# PWR_DC_DC_EXAR.net
KiCad netlist of a schematic drawn in Altium Designer
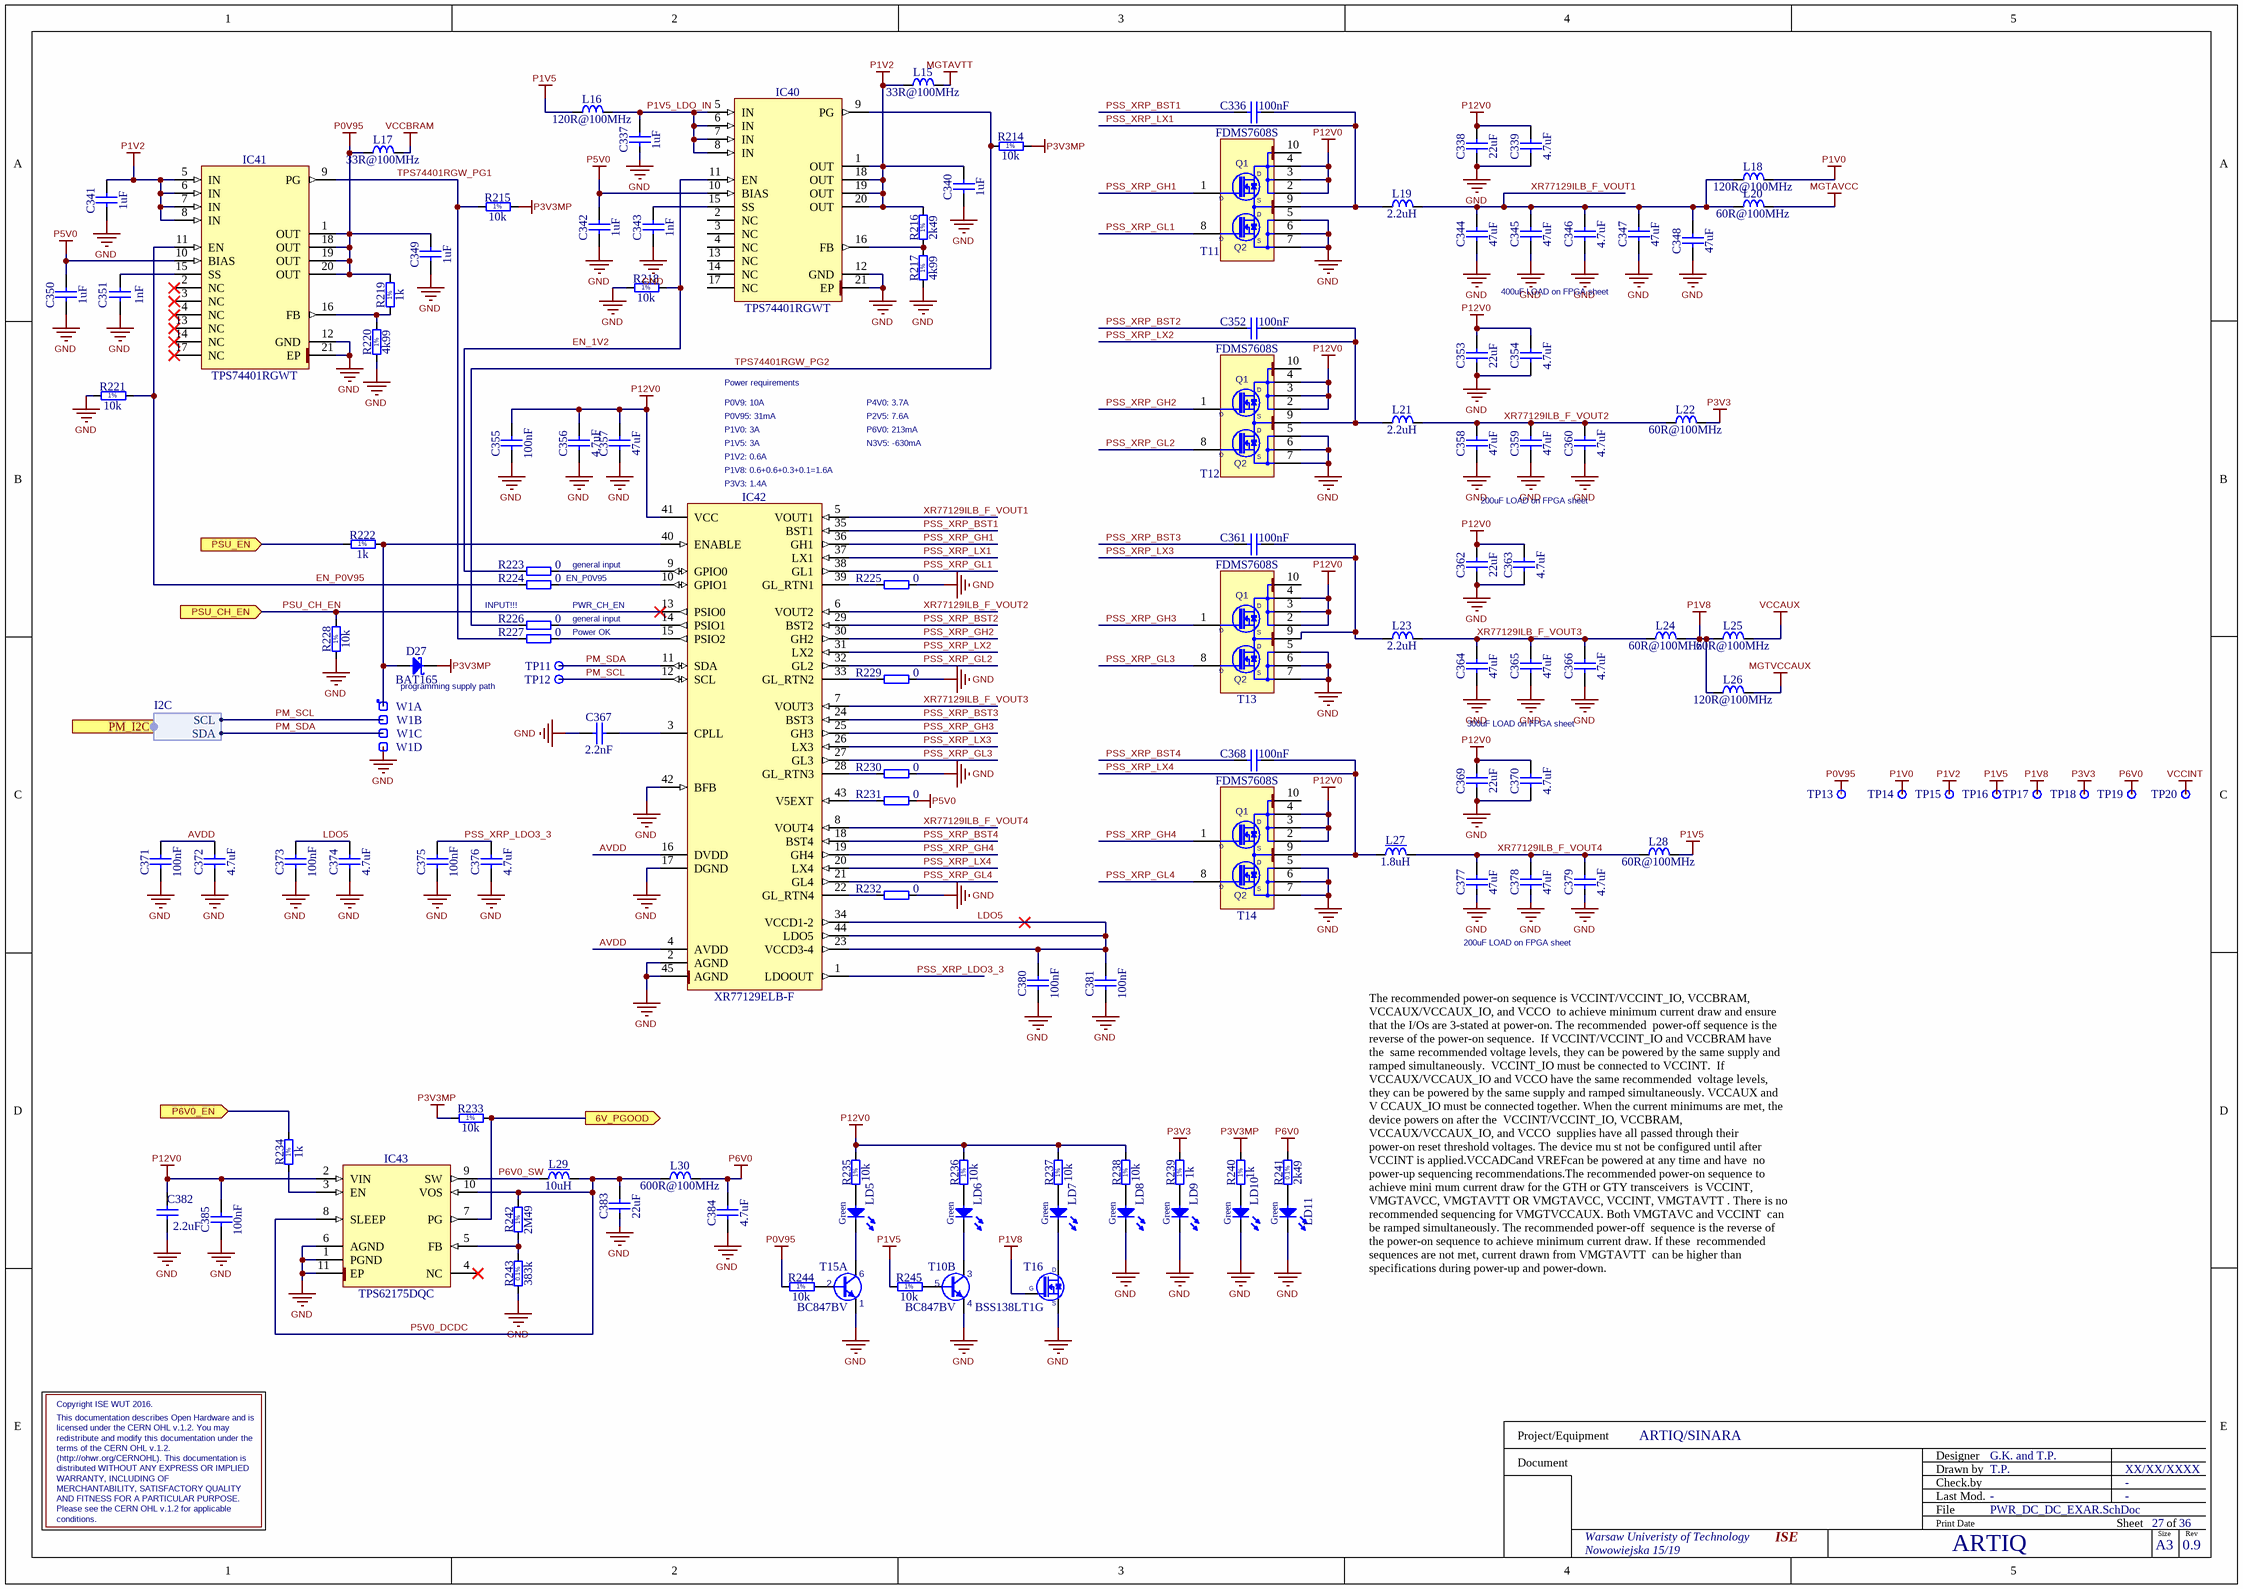
[diagram p0: PWR_DC_DC_EXAR.SchDoc]

(export (version "E")
  (design (tool "Eeschema 10.0.6"))
  (components
    (comp (ref "C336")
      (value "100nF")
      (footprint "CAPC1005X55N")
      (description "Non-polarised capacitor")
      (fields
        (field (name "MANUFACTURER PART NUMBER") "CC0402_100NF_16V_10%_X5R")
        (field (name "MANUFACTURER") "GENERIC")
        (field (name "AUTHOR") "CERN DEM JLC")
      )
      (libsource (lib "Capacitors") (part "Capacitor - non polarized"))
    )
    (comp (ref "C337")
      (value "1uF")
      (footprint "CAPC1005X55N")
      (description "Non-polarised capacitor")
      (fields
        (field (name "MANUFACTURER PART NUMBER") "CC0402_1UF_16V_10%_X5R")
        (field (name "MANUFACTURER") "GENERIC")
        (field (name "AUTHOR") "CERN DEM JLC")
      )
      (libsource (lib "Capacitors") (part "Capacitor - non polarized"))
    )
    (comp (ref "C338")
      (value "22uF")
      (footprint "CAPC2012X135N")
      (description "Non-polarised capacitor")
      (fields
        (field (name "MANUFACTURER PART NUMBER") "CC0805_22UF_16V_10%_X5R")
        (field (name "MANUFACTURER") "GENERIC")
        (field (name "AUTHOR") "CERN DEM JLC")
      )
      (libsource (lib "Capacitors") (part "Capacitor - non polarized"))
    )
    (comp (ref "C339")
      (value "4.7uF")
      (footprint "CAPC1709X95N")
      (description "Non-polarised capacitor")
      (fields
        (field (name "MANUFACTURER PART NUMBER") "CC0603_4.7UF_16V_10%_X5R")
        (field (name "MANUFACTURER") "GENERIC")
        (field (name "AUTHOR") "CERN DEM JLC")
      )
      (libsource (lib "Capacitors") (part "Capacitor - non polarized"))
    )
    (comp (ref "C340")
      (value "1uF")
      (footprint "CAPC1005X55N")
      (description "Non-polarised capacitor")
      (fields
        (field (name "MANUFACTURER PART NUMBER") "CC0402_1UF_16V_10%_X5R")
        (field (name "MANUFACTURER") "GENERIC")
        (field (name "AUTHOR") "CERN DEM JLC")
      )
      (libsource (lib "Capacitors") (part "Capacitor - non polarized"))
    )
    (comp (ref "C341")
      (value "1uF")
      (footprint "CAPC1005X55N")
      (description "Non-polarised capacitor")
      (fields
        (field (name "MANUFACTURER PART NUMBER") "CC0402_1UF_16V_10%_X5R")
        (field (name "MANUFACTURER") "GENERIC")
        (field (name "AUTHOR") "CERN DEM JLC")
      )
      (libsource (lib "Capacitors") (part "Capacitor - non polarized"))
    )
    (comp (ref "C342")
      (value "1uF")
      (footprint "CAPC1005X55N")
      (description "Non-polarised capacitor")
      (fields
        (field (name "MANUFACTURER PART NUMBER") "CC0402_1UF_16V_10%_X5R")
        (field (name "MANUFACTURER") "GENERIC")
        (field (name "AUTHOR") "CERN DEM JLC")
      )
      (libsource (lib "Capacitors") (part "Capacitor - non polarized"))
    )
    (comp (ref "C343")
      (value "1nF")
      (footprint "CAPC1005X55N")
      (description "Non-polarised capacitor")
      (fields
        (field (name "MANUFACTURER PART NUMBER") "CC0402_1NF_50V_10%_X7R")
        (field (name "MANUFACTURER") "GENERIC")
        (field (name "AUTHOR") "CERN DEM JLC")
      )
      (libsource (lib "Capacitors") (part "Capacitor - non polarized"))
    )
    (comp (ref "C344")
      (value "47uF")
      (footprint "CAPC2012X140N")
      (description "Non-polarised capacitor")
      (fields
        (field (name "MANUFACTURER PART NUMBER") "CC0805_47UF_6.3V_20%_X5R")
        (field (name "MANUFACTURER") "GENERIC")
        (field (name "AUTHOR") "CERN DEM JLC")
      )
      (libsource (lib "Capacitors") (part "Capacitor - non polarized"))
    )
    (comp (ref "C345")
      (value "47uF")
      (footprint "CAPC2012X140N")
      (description "Non-polarised capacitor")
      (fields
        (field (name "MANUFACTURER PART NUMBER") "CC0805_47UF_6.3V_20%_X5R")
        (field (name "MANUFACTURER") "GENERIC")
        (field (name "AUTHOR") "CERN DEM JLC")
      )
      (libsource (lib "Capacitors") (part "Capacitor - non polarized"))
    )
    (comp (ref "C346")
      (value "4.7uF")
      (footprint "CAPC1709X95N")
      (description "Non-polarised capacitor")
      (fields
        (field (name "MANUFACTURER PART NUMBER") "CC0603_4.7UF_16V_10%_X5R")
        (field (name "MANUFACTURER") "GENERIC")
        (field (name "AUTHOR") "CERN DEM JLC")
      )
      (libsource (lib "Capacitors") (part "Capacitor - non polarized"))
    )
    (comp (ref "C347")
      (value "47uF")
      (footprint "CAPC2012X140N")
      (description "Non-polarised capacitor")
      (fields
        (field (name "MANUFACTURER PART NUMBER") "CC0805_47UF_6.3V_20%_X5R")
        (field (name "MANUFACTURER") "GENERIC")
        (field (name "AUTHOR") "CERN DEM JLC")
      )
      (libsource (lib "Capacitors") (part "Capacitor - non polarized"))
    )
    (comp (ref "C348")
      (value "47uF")
      (footprint "CAPC2012X140N")
      (description "Non-polarised capacitor")
      (fields
        (field (name "MANUFACTURER PART NUMBER") "CC0805_47UF_6.3V_20%_X5R")
        (field (name "MANUFACTURER") "GENERIC")
        (field (name "AUTHOR") "CERN DEM JLC")
      )
      (libsource (lib "Capacitors") (part "Capacitor - non polarized"))
    )
    (comp (ref "C349")
      (value "1uF")
      (footprint "CAPC1005X55N")
      (description "Non-polarised capacitor")
      (fields
        (field (name "MANUFACTURER PART NUMBER") "CC0402_1UF_16V_10%_X5R")
        (field (name "MANUFACTURER") "GENERIC")
        (field (name "AUTHOR") "CERN DEM JLC")
      )
      (libsource (lib "Capacitors") (part "Capacitor - non polarized"))
    )
    (comp (ref "C350")
      (value "1uF")
      (footprint "CAPC1005X55N")
      (description "Non-polarised capacitor")
      (fields
        (field (name "MANUFACTURER PART NUMBER") "CC0402_1UF_16V_10%_X5R")
        (field (name "MANUFACTURER") "GENERIC")
        (field (name "AUTHOR") "CERN DEM JLC")
      )
      (libsource (lib "Capacitors") (part "Capacitor - non polarized"))
    )
    (comp (ref "C351")
      (value "1nF")
      (footprint "CAPC1005X55N")
      (description "Non-polarised capacitor")
      (fields
        (field (name "MANUFACTURER PART NUMBER") "CC0402_1NF_50V_10%_X7R")
        (field (name "MANUFACTURER") "GENERIC")
        (field (name "AUTHOR") "CERN DEM JLC")
      )
      (libsource (lib "Capacitors") (part "Capacitor - non polarized"))
    )
    (comp (ref "C352")
      (value "100nF")
      (footprint "CAPC1005X55N")
      (description "Non-polarised capacitor")
      (fields
        (field (name "MANUFACTURER PART NUMBER") "CC0402_100NF_16V_10%_X5R")
        (field (name "MANUFACTURER") "GENERIC")
        (field (name "AUTHOR") "CERN DEM JLC")
      )
      (libsource (lib "Capacitors") (part "Capacitor - non polarized"))
    )
    (comp (ref "C353")
      (value "22uF")
      (footprint "CAPC2012X135N")
      (description "Non-polarised capacitor")
      (fields
        (field (name "MANUFACTURER PART NUMBER") "CC0805_22UF_16V_10%_X5R")
        (field (name "MANUFACTURER") "GENERIC")
        (field (name "AUTHOR") "CERN DEM JLC")
      )
      (libsource (lib "Capacitors") (part "Capacitor - non polarized"))
    )
    (comp (ref "C354")
      (value "4.7uF")
      (footprint "CAPC1709X95N")
      (description "Non-polarised capacitor")
      (fields
        (field (name "MANUFACTURER PART NUMBER") "CC0603_4.7UF_16V_10%_X5R")
        (field (name "MANUFACTURER") "GENERIC")
        (field (name "AUTHOR") "CERN DEM JLC")
      )
      (libsource (lib "Capacitors") (part "Capacitor - non polarized"))
    )
    (comp (ref "C355")
      (value "100nF")
      (footprint "CAPC1005X55N")
      (description "Non-polarised capacitor")
      (fields
        (field (name "MANUFACTURER PART NUMBER") "CC0402_100NF_16V_10%_X5R")
        (field (name "MANUFACTURER") "GENERIC")
        (field (name "AUTHOR") "CERN DEM JLC")
      )
      (libsource (lib "Capacitors") (part "Capacitor - non polarized"))
    )
    (comp (ref "C356")
      (value "4.7uF")
      (footprint "CAPC1709X95N")
      (description "Non-polarised capacitor")
      (fields
        (field (name "MANUFACTURER PART NUMBER") "CC0603_4.7UF_16V_10%_X5R")
        (field (name "MANUFACTURER") "GENERIC")
        (field (name "AUTHOR") "CERN DEM JLC")
      )
      (libsource (lib "Capacitors") (part "Capacitor - non polarized"))
    )
    (comp (ref "C357")
      (value "47uF")
      (footprint "CAPC3216X180N")
      (description "Non-polarised capacitor")
      (fields
        (field (name "MANUFACTURER PART NUMBER") "CC1206_47UF_25V_20%_X5R")
        (field (name "MANUFACTURER") "GENERIC")
        (field (name "AUTHOR") "CERN DEM JLC")
      )
      (libsource (lib "Capacitors") (part "Capacitor - non polarized"))
    )
    (comp (ref "C358")
      (value "47uF")
      (footprint "CAPC2012X140N")
      (description "Non-polarised capacitor")
      (fields
        (field (name "MANUFACTURER PART NUMBER") "CC0805_47UF_6.3V_20%_X5R")
        (field (name "MANUFACTURER") "GENERIC")
        (field (name "AUTHOR") "CERN DEM JLC")
      )
      (libsource (lib "Capacitors") (part "Capacitor - non polarized"))
    )
    (comp (ref "C359")
      (value "47uF")
      (footprint "CAPC2012X140N")
      (description "Non-polarised capacitor")
      (fields
        (field (name "MANUFACTURER PART NUMBER") "CC0805_47UF_6.3V_20%_X5R")
        (field (name "MANUFACTURER") "GENERIC")
        (field (name "AUTHOR") "CERN DEM JLC")
      )
      (libsource (lib "Capacitors") (part "Capacitor - non polarized"))
    )
    (comp (ref "C360")
      (value "4.7uF")
      (footprint "CAPC1709X95N")
      (description "Non-polarised capacitor")
      (fields
        (field (name "MANUFACTURER PART NUMBER") "CC0603_4.7UF_16V_10%_X5R")
        (field (name "MANUFACTURER") "GENERIC")
        (field (name "AUTHOR") "CERN DEM JLC")
      )
      (libsource (lib "Capacitors") (part "Capacitor - non polarized"))
    )
    (comp (ref "C361")
      (value "100nF")
      (footprint "CAPC1005X55N")
      (description "Non-polarised capacitor")
      (fields
        (field (name "MANUFACTURER PART NUMBER") "CC0402_100NF_16V_10%_X5R")
        (field (name "MANUFACTURER") "GENERIC")
        (field (name "AUTHOR") "CERN DEM JLC")
      )
      (libsource (lib "Capacitors") (part "Capacitor - non polarized"))
    )
    (comp (ref "C362")
      (value "22uF")
      (footprint "CAPC2012X135N")
      (description "Non-polarised capacitor")
      (fields
        (field (name "MANUFACTURER PART NUMBER") "CC0805_22UF_16V_10%_X5R")
        (field (name "MANUFACTURER") "GENERIC")
        (field (name "AUTHOR") "CERN DEM JLC")
      )
      (libsource (lib "Capacitors") (part "Capacitor - non polarized"))
    )
    (comp (ref "C363")
      (value "4.7uF")
      (footprint "CAPC1709X95N")
      (description "Non-polarised capacitor")
      (fields
        (field (name "MANUFACTURER PART NUMBER") "CC0603_4.7UF_16V_10%_X5R")
        (field (name "MANUFACTURER") "GENERIC")
        (field (name "AUTHOR") "CERN DEM JLC")
      )
      (libsource (lib "Capacitors") (part "Capacitor - non polarized"))
    )
    (comp (ref "C364")
      (value "47uF")
      (footprint "CAPC2012X140N")
      (description "Non-polarised capacitor")
      (fields
        (field (name "MANUFACTURER PART NUMBER") "CC0805_47UF_6.3V_20%_X5R")
        (field (name "MANUFACTURER") "GENERIC")
        (field (name "AUTHOR") "CERN DEM JLC")
      )
      (libsource (lib "Capacitors") (part "Capacitor - non polarized"))
    )
    (comp (ref "C365")
      (value "47uF")
      (footprint "CAPC2012X140N")
      (description "Non-polarised capacitor")
      (fields
        (field (name "MANUFACTURER PART NUMBER") "CC0805_47UF_6.3V_20%_X5R")
        (field (name "MANUFACTURER") "GENERIC")
        (field (name "AUTHOR") "CERN DEM JLC")
      )
      (libsource (lib "Capacitors") (part "Capacitor - non polarized"))
    )
    (comp (ref "C366")
      (value "4.7uF")
      (footprint "CAPC1709X95N")
      (description "Non-polarised capacitor")
      (fields
        (field (name "MANUFACTURER PART NUMBER") "CC0603_4.7UF_16V_10%_X5R")
        (field (name "MANUFACTURER") "GENERIC")
        (field (name "AUTHOR") "CERN DEM JLC")
      )
      (libsource (lib "Capacitors") (part "Capacitor - non polarized"))
    )
    (comp (ref "C367")
      (value "2.2nF")
      (footprint "CAPC1005X55N")
      (description "Non-polarised capacitor")
      (fields
        (field (name "MANUFACTURER PART NUMBER") "CC0402_2.2NF_50V_10%_X7R")
        (field (name "MANUFACTURER") "GENERIC")
        (field (name "AUTHOR") "CERN DEM JLC")
      )
      (libsource (lib "Capacitors") (part "Capacitor - non polarized"))
    )
    (comp (ref "C368")
      (value "100nF")
      (footprint "CAPC1005X55N")
      (description "Non-polarised capacitor")
      (fields
        (field (name "MANUFACTURER PART NUMBER") "CC0402_100NF_16V_10%_X5R")
        (field (name "MANUFACTURER") "GENERIC")
        (field (name "AUTHOR") "CERN DEM JLC")
      )
      (libsource (lib "Capacitors") (part "Capacitor - non polarized"))
    )
    (comp (ref "C369")
      (value "22uF")
      (footprint "CAPC2012X135N")
      (description "Non-polarised capacitor")
      (fields
        (field (name "MANUFACTURER PART NUMBER") "CC0805_22UF_16V_10%_X5R")
        (field (name "MANUFACTURER") "GENERIC")
        (field (name "AUTHOR") "CERN DEM JLC")
      )
      (libsource (lib "Capacitors") (part "Capacitor - non polarized"))
    )
    (comp (ref "C370")
      (value "4.7uF")
      (footprint "CAPC1709X95N")
      (description "Non-polarised capacitor")
      (fields
        (field (name "MANUFACTURER PART NUMBER") "CC0603_4.7UF_16V_10%_X5R")
        (field (name "MANUFACTURER") "GENERIC")
        (field (name "AUTHOR") "CERN DEM JLC")
      )
      (libsource (lib "Capacitors") (part "Capacitor - non polarized"))
    )
    (comp (ref "C371")
      (value "100nF")
      (footprint "CAPC1005X55N")
      (description "Non-polarised capacitor")
      (fields
        (field (name "MANUFACTURER PART NUMBER") "CC0402_100NF_16V_10%_X5R")
        (field (name "MANUFACTURER") "GENERIC")
        (field (name "AUTHOR") "CERN DEM JLC")
      )
      (libsource (lib "Capacitors") (part "Capacitor - non polarized"))
    )
    (comp (ref "C372")
      (value "4.7uF")
      (footprint "CAPC1709X95N")
      (description "Non-polarised capacitor")
      (fields
        (field (name "MANUFACTURER PART NUMBER") "CC0603_4.7UF_16V_10%_X5R")
        (field (name "MANUFACTURER") "GENERIC")
        (field (name "AUTHOR") "CERN DEM JLC")
      )
      (libsource (lib "Capacitors") (part "Capacitor - non polarized"))
    )
    (comp (ref "C373")
      (value "100nF")
      (footprint "CAPC1005X55N")
      (description "Non-polarised capacitor")
      (fields
        (field (name "MANUFACTURER PART NUMBER") "CC0402_100NF_16V_10%_X5R")
        (field (name "MANUFACTURER") "GENERIC")
        (field (name "AUTHOR") "CERN DEM JLC")
      )
      (libsource (lib "Capacitors") (part "Capacitor - non polarized"))
    )
    (comp (ref "C374")
      (value "4.7uF")
      (footprint "CAPC1709X95N")
      (description "Non-polarised capacitor")
      (fields
        (field (name "MANUFACTURER PART NUMBER") "CC0603_4.7UF_16V_10%_X5R")
        (field (name "MANUFACTURER") "GENERIC")
        (field (name "AUTHOR") "CERN DEM JLC")
      )
      (libsource (lib "Capacitors") (part "Capacitor - non polarized"))
    )
    (comp (ref "C375")
      (value "100nF")
      (footprint "CAPC1005X55N")
      (description "Non-polarised capacitor")
      (fields
        (field (name "MANUFACTURER PART NUMBER") "CC0402_100NF_16V_10%_X5R")
        (field (name "MANUFACTURER") "GENERIC")
        (field (name "AUTHOR") "CERN DEM JLC")
      )
      (libsource (lib "Capacitors") (part "Capacitor - non polarized"))
    )
    (comp (ref "C376")
      (value "4.7uF")
      (footprint "CAPC1709X95N")
      (description "Non-polarised capacitor")
      (fields
        (field (name "MANUFACTURER PART NUMBER") "CC0603_4.7UF_16V_10%_X5R")
        (field (name "MANUFACTURER") "GENERIC")
        (field (name "AUTHOR") "CERN DEM JLC")
      )
      (libsource (lib "Capacitors") (part "Capacitor - non polarized"))
    )
    (comp (ref "C377")
      (value "47uF")
      (footprint "CAPC2012X140N")
      (description "Non-polarised capacitor")
      (fields
        (field (name "MANUFACTURER PART NUMBER") "CC0805_47UF_6.3V_20%_X5R")
        (field (name "MANUFACTURER") "GENERIC")
        (field (name "AUTHOR") "CERN DEM JLC")
      )
      (libsource (lib "Capacitors") (part "Capacitor - non polarized"))
    )
    (comp (ref "C378")
      (value "47uF")
      (footprint "CAPC2012X140N")
      (description "Non-polarised capacitor")
      (fields
        (field (name "MANUFACTURER PART NUMBER") "CC0805_47UF_6.3V_20%_X5R")
        (field (name "MANUFACTURER") "GENERIC")
        (field (name "AUTHOR") "CERN DEM JLC")
      )
      (libsource (lib "Capacitors") (part "Capacitor - non polarized"))
    )
    (comp (ref "C379")
      (value "4.7uF")
      (footprint "CAPC1709X95N")
      (description "Non-polarised capacitor")
      (fields
        (field (name "MANUFACTURER PART NUMBER") "CC0603_4.7UF_16V_10%_X5R")
        (field (name "MANUFACTURER") "GENERIC")
        (field (name "AUTHOR") "CERN DEM JLC")
      )
      (libsource (lib "Capacitors") (part "Capacitor - non polarized"))
    )
    (comp (ref "C380")
      (value "100nF")
      (footprint "CAPC1005X55N")
      (description "Non-polarised capacitor")
      (fields
        (field (name "MANUFACTURER PART NUMBER") "CC0402_100NF_16V_10%_X5R")
        (field (name "MANUFACTURER") "GENERIC")
        (field (name "AUTHOR") "CERN DEM JLC")
      )
      (libsource (lib "Capacitors") (part "Capacitor - non polarized"))
    )
    (comp (ref "C381")
      (value "100nF")
      (footprint "CAPC1005X55N")
      (description "Non-polarised capacitor")
      (fields
        (field (name "MANUFACTURER PART NUMBER") "CC0402_100NF_16V_10%_X5R")
        (field (name "MANUFACTURER") "GENERIC")
        (field (name "AUTHOR") "CERN DEM JLC")
      )
      (libsource (lib "Capacitors") (part "Capacitor - non polarized"))
    )
    (comp (ref "C382")
      (value "2.2uF")
      (footprint "CAPC1005X55N")
      (description "Non-polarised capacitor")
      (fields
        (field (name "PART NUMBER") "CC0402_2.2UF_6.3V_10%_X5R")
        (field (name "VOLTAGE") "6.3V")
        (field (name "AUTHOR") "CERN DEM JMW")
      )
      (libsource (lib "Capacitors") (part "Capacitor - non polarized"))
    )
    (comp (ref "C383")
      (value "22uF")
      (footprint "CAPC2012X135N")
      (description "Non-polarised capacitor")
      (fields
        (field (name "MANUFACTURER PART NUMBER") "CC0805_22UF_16V_10%_X5R")
        (field (name "MANUFACTURER") "GENERIC")
        (field (name "AUTHOR") "CERN DEM JLC")
      )
      (libsource (lib "Capacitors") (part "Capacitor - non polarized"))
    )
    (comp (ref "C384")
      (value "4.7uF")
      (footprint "CAPC1709X95N")
      (description "Non-polarised capacitor")
      (fields
        (field (name "MANUFACTURER PART NUMBER") "CC0603_4.7UF_16V_10%_X5R")
        (field (name "MANUFACTURER") "GENERIC")
        (field (name "AUTHOR") "CERN DEM JLC")
      )
      (libsource (lib "Capacitors") (part "Capacitor - non polarized"))
    )
    (comp (ref "C385")
      (value "100nF")
      (footprint "CAPC1005X55N")
      (description "Non-polarised capacitor")
      (fields
        (field (name "MANUFACTURER PART NUMBER") "CC0402_100NF_16V_10%_X5R")
        (field (name "MANUFACTURER") "GENERIC")
        (field (name "AUTHOR") "CERN DEM JLC")
      )
      (libsource (lib "Capacitors") (part "Capacitor - non polarized"))
    )
    (comp (ref "D27")
      (value "BAT165")
      (footprint "SOD2512X110N")
      (description "Schottky Diode")
      (fields
        (field (name "MANUFACTURER") "INFINEON")
        (field (name "VOLTAGE") "40V")
        (field (name "AUTHOR") "CERN DEM JLC")
      )
      (libsource (lib "ICs And Semiconductors") (part "Diode Schottky"))
    )
    (comp (ref "IC40")
      (value "TPS74401RGWT")
      (footprint "QFN65P500X500X100-21N-S325")
      (description "Single Output LDO, 3.0A, Adj.(0.8 to 3.3V), Fast Transient Response, Programmable SoftStart")
      (fields (field (name "MANUFACTURER") "TEXAS INSTRUMENTS") (field (name "AUTHOR") "CERN DEM JLC"))
      (libsource (lib "ICs And Semiconductors") (part "TPS74401RGW"))
    )
    (comp (ref "IC41")
      (value "TPS74401RGWT")
      (footprint "QFN65P500X500X100-21N-S325")
      (description "Single Output LDO, 3.0A, Adj.(0.8 to 3.3V), Fast Transient Response, Programmable SoftStart")
      (fields (field (name "MANUFACTURER") "TEXAS INSTRUMENTS") (field (name "AUTHOR") "CERN DEM JLC"))
      (libsource (lib "ICs And Semiconductors") (part "TPS74401RGW"))
    )
    (comp (ref "IC42")
      (value "XR77129ELB-F")
      (footprint "QFN50P700X700X80-45N-S520")
      (description "40V Quad Channel Digital PWM/PFM Universal PMIC")
      (fields (field (name "MANUFACTURER") "EXAR") (field (name "AUTHOR") "CERN DEM JLC"))
      (libsource (lib "ICs And Semiconductors") (part "XR77129ELB-F"))
    )
    (comp (ref "IC43")
      (value "TPS62175DQC")
      (footprint "SON50P200X300X80-11N-R94X250")
      (description "4.75-28VDC to 1-6VDC, 500mA Step-Down Converter With Sleep Mode")
      (fields (field (name "MANUFACTURER") "TEXAS INSTRUMENTS") (field (name "AUTHOR") "CERN DEM JMW"))
      (libsource (lib "ICs And Semiconductors") (part "TPS62175"))
    )
    (comp (ref "L15")
      (value "33R@100MHz")
      (footprint "INDC1608X95N")
      (description "Inductor")
      (fields
        (field (name "MANUFACTURER PART NUMBER") "BLM18PG330SN1D")
        (field (name "MANUFACTURER") "MURATA")
        (field (name "AUTHOR") "CERN DEM JMW")
      )
      (libsource (lib "Inductors & Transformers") (part "Inductor"))
    )
    (comp (ref "L16")
      (value "120R@100MHz")
      (footprint "INDC1608X95N")
      (description "Inductor")
      (fields
        (field (name "MANUFACTURER PART NUMBER") "BLM18PG121SN1D")
        (field (name "MANUFACTURER") "MURATA")
        (field (name "AUTHOR") "CERN DEM BC")
      )
      (libsource (lib "") (part "Inductor_1"))
    )
    (comp (ref "L17")
      (value "33R@100MHz")
      (footprint "INDC1608X95N")
      (description "Inductor")
      (fields
        (field (name "MANUFACTURER PART NUMBER") "BLM18PG330SN1D")
        (field (name "MANUFACTURER") "MURATA")
        (field (name "AUTHOR") "CERN DEM JMW")
      )
      (libsource (lib "Inductors & Transformers") (part "Inductor"))
    )
    (comp (ref "L18")
      (value "120R@100MHz")
      (footprint "INDC1608X95N")
      (description "Inductor")
      (fields
        (field (name "MANUFACTURER PART NUMBER") "BLM18PG121SN1D")
        (field (name "MANUFACTURER") "MURATA")
        (field (name "AUTHOR") "CERN DEM BC")
      )
      (libsource (lib "") (part "Inductor_1"))
    )
    (comp (ref "L19")
      (value "2.2uH")
      (footprint "IND_BOURNS_SRP6540")
      (description "Inductor")
      (fields
        (field (name "MANUFACTURER PART NUMBER") "SRP6540-2R2M")
        (field (name "MANUFACTURER") "BOURNS")
        (field (name "AUTHOR") "CERN DEM JMW")
      )
      (libsource (lib "Inductors & Transformers") (part "Inductor"))
    )
    (comp (ref "L20")
      (value "60R@100MHz")
      (footprint "INDC4516X180N")
      (description "Inductor")
      (fields
        (field (name "MANUFACTURER PART NUMBER") "BLM41PG600SN1L")
        (field (name "MANUFACTURER") "MURATA")
        (field (name "AUTHOR") "CERN DEM JLC")
      )
      (libsource (lib "Inductors & Transformers") (part "Inductor"))
    )
    (comp (ref "L21")
      (value "2.2uH")
      (footprint "IND_BOURNS_SRP6540")
      (description "Inductor")
      (fields
        (field (name "MANUFACTURER PART NUMBER") "SRP6540-2R2M")
        (field (name "MANUFACTURER") "BOURNS")
        (field (name "AUTHOR") "CERN DEM JMW")
      )
      (libsource (lib "Inductors & Transformers") (part "Inductor"))
    )
    (comp (ref "L22")
      (value "60R@100MHz")
      (footprint "INDC4516X180N")
      (description "Inductor")
      (fields
        (field (name "MANUFACTURER PART NUMBER") "BLM41PG600SN1L")
        (field (name "MANUFACTURER") "MURATA")
        (field (name "AUTHOR") "CERN DEM JLC")
      )
      (libsource (lib "Inductors & Transformers") (part "Inductor"))
    )
    (comp (ref "L23")
      (value "2.2uH")
      (footprint "IND_BOURNS_SRP6540")
      (description "Inductor")
      (fields
        (field (name "MANUFACTURER PART NUMBER") "SRP6540-2R2M")
        (field (name "MANUFACTURER") "BOURNS")
        (field (name "AUTHOR") "CERN DEM JMW")
      )
      (libsource (lib "Inductors & Transformers") (part "Inductor"))
    )
    (comp (ref "L24")
      (value "60R@100MHz")
      (footprint "INDC4516X180N")
      (description "Inductor")
      (fields
        (field (name "MANUFACTURER PART NUMBER") "BLM41PG600SN1L")
        (field (name "MANUFACTURER") "MURATA")
        (field (name "AUTHOR") "CERN DEM JLC")
      )
      (libsource (lib "Inductors & Transformers") (part "Inductor"))
    )
    (comp (ref "L25")
      (value "60R@100MHz")
      (footprint "INDC4516X180N")
      (description "Inductor")
      (fields
        (field (name "MANUFACTURER PART NUMBER") "BLM41PG600SN1L")
        (field (name "MANUFACTURER") "MURATA")
        (field (name "AUTHOR") "CERN DEM JLC")
      )
      (libsource (lib "Inductors & Transformers") (part "Inductor"))
    )
    (comp (ref "L26")
      (value "120R@100MHz")
      (footprint "INDC1608X95N")
      (description "Inductor")
      (fields
        (field (name "MANUFACTURER PART NUMBER") "BLM18PG121SN1D")
        (field (name "MANUFACTURER") "MURATA")
        (field (name "AUTHOR") "CERN DEM BC")
      )
      (libsource (lib "") (part "Inductor_1"))
    )
    (comp (ref "L27")
      (value "1.8uH")
      (footprint "IND_COILCRAFT_XAL7070")
      (description "Inductor With Core")
      (fields
        (field (name "MANUFACTURER PART NUMBER") "XAL7070-182MEC")
        (field (name "MANUFACTURER") "COILCRAFT")
        (field (name "AUTHOR") "CERN DEM JLC")
      )
      (libsource (lib "Inductors & Transformers") (part "Inductor With Magnetic core"))
    )
    (comp (ref "L28")
      (value "60R@100MHz")
      (footprint "INDC4516X180N")
      (description "Inductor")
      (fields
        (field (name "MANUFACTURER PART NUMBER") "BLM41PG600SN1L")
        (field (name "MANUFACTURER") "MURATA")
        (field (name "AUTHOR") "CERN DEM JLC")
      )
      (libsource (lib "Inductors & Transformers") (part "Inductor"))
    )
    (comp (ref "L29")
      (value "10uH")
      (footprint "IND_WURTH_WE-SPC-4838")
      (description "Inductor With Core")
      (fields
        (field (name "PART NUMBER") "IND_10UH_20%_WURTH_WE-SPC_74408943100")
        (field (name "POWER") "1.65A")
        (field (name "AUTHOR") "CERN DEM MR")
      )
      (libsource (lib "Inductors & Transformers") (part "Inductor With Magnetic core"))
    )
    (comp (ref "L30")
      (value "600R@100MHz")
      (footprint "INDC2012X110N")
      (description "Inductor")
      (fields
        (field (name "MANUFACTURER PART NUMBER") "742792040")
        (field (name "MANUFACTURER") "WURTH ELEKTRONIK")
        (field (name "AUTHOR") "CERN DEM JLC")
      )
      (libsource (lib "Inductors & Transformers") (part "Inductor"))
    )
    (comp (ref "LD5")
      (value "Green")
      (footprint "LED_OSRAM_LGL29K")
      (description "LED Green 1C 2A")
      (fields
        (field (name "MANUFACTURER PART NUMBER") "LG L29K-G2J1-24-Z")
        (field (name "MANUFACTURER") "OSRAM")
        (field (name "AUTHOR") "CERN DEM JLC")
      )
      (libsource (lib "ICs And Semiconductors") (part "LED Green 1C 2A"))
    )
    (comp (ref "LD6")
      (value "Green")
      (footprint "LED_OSRAM_LGL29K")
      (description "LED Green 1C 2A")
      (fields
        (field (name "MANUFACTURER PART NUMBER") "LG L29K-G2J1-24-Z")
        (field (name "MANUFACTURER") "OSRAM")
        (field (name "AUTHOR") "CERN DEM JLC")
      )
      (libsource (lib "ICs And Semiconductors") (part "LED Green 1C 2A"))
    )
    (comp (ref "LD7")
      (value "Green")
      (footprint "LED_OSRAM_LGL29K")
      (description "LED Green 1C 2A")
      (fields
        (field (name "MANUFACTURER PART NUMBER") "LG L29K-G2J1-24-Z")
        (field (name "MANUFACTURER") "OSRAM")
        (field (name "AUTHOR") "CERN DEM JLC")
      )
      (libsource (lib "ICs And Semiconductors") (part "LED Green 1C 2A"))
    )
    (comp (ref "LD8")
      (value "Green")
      (footprint "LED_OSRAM_LGL29K")
      (description "LED Green 1C 2A")
      (fields
        (field (name "MANUFACTURER PART NUMBER") "LG L29K-G2J1-24-Z")
        (field (name "MANUFACTURER") "OSRAM")
        (field (name "AUTHOR") "CERN DEM JLC")
      )
      (libsource (lib "ICs And Semiconductors") (part "LED Green 1C 2A"))
    )
    (comp (ref "LD9")
      (value "Green")
      (footprint "LED_OSRAM_LGL29K")
      (description "LED Green 1C 2A")
      (fields
        (field (name "MANUFACTURER PART NUMBER") "LG L29K-G2J1-24-Z")
        (field (name "MANUFACTURER") "OSRAM")
        (field (name "AUTHOR") "CERN DEM JLC")
      )
      (libsource (lib "ICs And Semiconductors") (part "LED Green 1C 2A"))
    )
    (comp (ref "LD10")
      (value "Green")
      (footprint "LED_OSRAM_LGL29K")
      (description "LED Green 1C 2A")
      (fields
        (field (name "MANUFACTURER PART NUMBER") "LG L29K-G2J1-24-Z")
        (field (name "MANUFACTURER") "OSRAM")
        (field (name "AUTHOR") "CERN DEM JLC")
      )
      (libsource (lib "ICs And Semiconductors") (part "LED Green 1C 2A"))
    )
    (comp (ref "LD11")
      (value "Green")
      (footprint "LED_OSRAM_LGL29K")
      (description "LED Green 1C 2A")
      (fields
        (field (name "MANUFACTURER PART NUMBER") "LG L29K-G2J1-24-Z")
        (field (name "MANUFACTURER") "OSRAM")
        (field (name "AUTHOR") "CERN DEM JLC")
      )
      (libsource (lib "ICs And Semiconductors") (part "LED Green 1C 2A"))
    )
    (comp (ref "R214")
      (value "10k")
      (footprint "RESC1005X40N")
      (description "Resistor - 1%")
      (fields
        (field (name "MANUFACTURER PART NUMBER") "R0402_10K_1%_0.0625W_100PPM")
        (field (name "MANUFACTURER") "GENERIC")
        (field (name "AUTHOR") "CERN DEM JLC")
      )
      (libsource (lib "Resistors") (part "Resistor - 1%"))
    )
    (comp (ref "R215")
      (value "10k")
      (footprint "RESC1005X40N")
      (description "Resistor - 1%")
      (fields
        (field (name "MANUFACTURER PART NUMBER") "R0402_10K_1%_0.0625W_100PPM")
        (field (name "MANUFACTURER") "GENERIC")
        (field (name "AUTHOR") "CERN DEM JLC")
      )
      (libsource (lib "Resistors") (part "Resistor - 1%"))
    )
    (comp (ref "R216")
      (value "2k49")
      (footprint "RESC1608X55N")
      (description "Resistor - 1%")
      (fields
        (field (name "MANUFACTURER PART NUMBER") "R0603_2K49_1%_0.063W_50PPM")
        (field (name "MANUFACTURER") "GENERIC")
        (field (name "AUTHOR") "CERN DEM JLC")
      )
      (libsource (lib "Resistors") (part "Resistor - 1%"))
    )
    (comp (ref "R217")
      (value "4k99")
      (footprint "RESC1608X55N")
      (description "Resistor - 1%")
      (fields
        (field (name "MANUFACTURER PART NUMBER") "R0603_4K99_1%_0.063W_50PPM")
        (field (name "MANUFACTURER") "GENERIC")
        (field (name "AUTHOR") "CERN DEM JLC")
      )
      (libsource (lib "Resistors") (part "Resistor - 1%"))
    )
    (comp (ref "R218")
      (value "10k")
      (footprint "RESC1005X40N")
      (description "Resistor - 1%")
      (fields
        (field (name "MANUFACTURER PART NUMBER") "R0402_10K_1%_0.0625W_100PPM")
        (field (name "MANUFACTURER") "GENERIC")
        (field (name "AUTHOR") "CERN DEM JLC")
      )
      (libsource (lib "Resistors") (part "Resistor - 1%"))
    )
    (comp (ref "R219")
      (value "1k")
      (footprint "RESC1005X40N")
      (description "Resistor - 1%")
      (fields
        (field (name "MANUFACTURER PART NUMBER") "R0402_1K_1%_0.0625W_100PPM")
        (field (name "MANUFACTURER") "GENERIC")
        (field (name "AUTHOR") "CERN DEM JLC")
      )
      (libsource (lib "Resistors") (part "Resistor - 1%"))
    )
    (comp (ref "R220")
      (value "4k99")
      (footprint "RESC1608X55N")
      (description "Resistor - 1%")
      (fields
        (field (name "MANUFACTURER PART NUMBER") "R0603_4K99_1%_0.063W_50PPM")
        (field (name "MANUFACTURER") "GENERIC")
        (field (name "AUTHOR") "CERN DEM JLC")
      )
      (libsource (lib "Resistors") (part "Resistor - 1%"))
    )
    (comp (ref "R221")
      (value "10k")
      (footprint "RESC1005X40N")
      (description "Resistor - 1%")
      (fields
        (field (name "MANUFACTURER PART NUMBER") "R0402_10K_1%_0.0625W_100PPM")
        (field (name "MANUFACTURER") "GENERIC")
        (field (name "AUTHOR") "CERN DEM JLC")
      )
      (libsource (lib "Resistors") (part "Resistor - 1%"))
    )
    (comp (ref "R222")
      (value "1k")
      (footprint "RESC1005X40N")
      (description "Resistor - 1%")
      (fields
        (field (name "MANUFACTURER PART NUMBER") "R0402_1K_1%_0.0625W_100PPM")
        (field (name "MANUFACTURER") "GENERIC")
        (field (name "AUTHOR") "CERN DEM JLC")
      )
      (libsource (lib "Resistors") (part "Resistor - 1%"))
    )
    (comp (ref "R223")
      (value "0")
      (footprint "RESC1005X40N")
      (description "Resistor")
      (fields
        (field (name "MANUFACTURER PART NUMBER") "R0402_0R_JUMPER")
        (field (name "MANUFACTURER") "GENERIC")
        (field (name "AUTHOR") "CERN DEM JLC")
      )
      (libsource (lib "Resistors") (part "Resistor"))
    )
    (comp (ref "R224")
      (value "0")
      (footprint "RESC1005X40N")
      (description "Resistor")
      (fields
        (field (name "MANUFACTURER PART NUMBER") "R0402_0R_JUMPER")
        (field (name "MANUFACTURER") "GENERIC")
        (field (name "AUTHOR") "CERN DEM JLC")
      )
      (libsource (lib "Resistors") (part "Resistor"))
    )
    (comp (ref "R225")
      (value "0")
      (footprint "RESC1005X40N")
      (description "Resistor")
      (fields
        (field (name "MANUFACTURER PART NUMBER") "R0402_0R_JUMPER")
        (field (name "MANUFACTURER") "GENERIC")
        (field (name "AUTHOR") "CERN DEM JLC")
      )
      (libsource (lib "Resistors") (part "Resistor"))
    )
    (comp (ref "R226")
      (value "0")
      (footprint "RESC1005X40N")
      (description "Resistor")
      (fields
        (field (name "MANUFACTURER PART NUMBER") "R0402_0R_JUMPER")
        (field (name "MANUFACTURER") "GENERIC")
        (field (name "AUTHOR") "CERN DEM JLC")
      )
      (libsource (lib "Resistors") (part "Resistor"))
    )
    (comp (ref "R227")
      (value "0")
      (footprint "RESC1005X40N")
      (description "Resistor")
      (fields
        (field (name "MANUFACTURER PART NUMBER") "R0402_0R_JUMPER")
        (field (name "MANUFACTURER") "GENERIC")
        (field (name "AUTHOR") "CERN DEM JLC")
      )
      (libsource (lib "Resistors") (part "Resistor"))
    )
    (comp (ref "R228")
      (value "10k")
      (footprint "RESC1005X40N")
      (description "Resistor - 1%")
      (fields
        (field (name "MANUFACTURER PART NUMBER") "R0402_10K_1%_0.0625W_100PPM")
        (field (name "MANUFACTURER") "GENERIC")
        (field (name "AUTHOR") "CERN DEM JLC")
      )
      (libsource (lib "Resistors") (part "Resistor - 1%"))
    )
    (comp (ref "R229")
      (value "0")
      (footprint "RESC1005X40N")
      (description "Resistor")
      (fields
        (field (name "MANUFACTURER PART NUMBER") "R0402_0R_JUMPER")
        (field (name "MANUFACTURER") "GENERIC")
        (field (name "AUTHOR") "CERN DEM JLC")
      )
      (libsource (lib "Resistors") (part "Resistor"))
    )
    (comp (ref "R230")
      (value "0")
      (footprint "RESC1005X40N")
      (description "Resistor")
      (fields
        (field (name "MANUFACTURER PART NUMBER") "R0402_0R_JUMPER")
        (field (name "MANUFACTURER") "GENERIC")
        (field (name "AUTHOR") "CERN DEM JLC")
      )
      (libsource (lib "Resistors") (part "Resistor"))
    )
    (comp (ref "R231")
      (value "0")
      (footprint "RESC1005X40N")
      (description "Resistor")
      (fields
        (field (name "MANUFACTURER PART NUMBER") "R0402_0R_JUMPER")
        (field (name "MANUFACTURER") "GENERIC")
        (field (name "AUTHOR") "CERN DEM JLC")
      )
      (libsource (lib "Resistors") (part "Resistor"))
    )
    (comp (ref "R232")
      (value "0")
      (footprint "RESC1005X40N")
      (description "Resistor")
      (fields
        (field (name "MANUFACTURER PART NUMBER") "R0402_0R_JUMPER")
        (field (name "MANUFACTURER") "GENERIC")
        (field (name "AUTHOR") "CERN DEM JLC")
      )
      (libsource (lib "Resistors") (part "Resistor"))
    )
    (comp (ref "R233")
      (value "10k")
      (footprint "RESC1005X40N")
      (description "Resistor - 1%")
      (fields
        (field (name "MANUFACTURER PART NUMBER") "R0402_10K_1%_0.0625W_100PPM")
        (field (name "MANUFACTURER") "GENERIC")
        (field (name "AUTHOR") "CERN DEM JLC")
      )
      (libsource (lib "Resistors") (part "Resistor - 1%"))
    )
    (comp (ref "R234")
      (value "1k")
      (footprint "RESC1005X40N")
      (description "Resistor - 1%")
      (fields
        (field (name "MANUFACTURER PART NUMBER") "R0402_1K_1%_0.0625W_100PPM")
        (field (name "MANUFACTURER") "GENERIC")
        (field (name "AUTHOR") "CERN DEM JLC")
      )
      (libsource (lib "Resistors") (part "Resistor - 1%"))
    )
    (comp (ref "R235")
      (value "10k")
      (footprint "RESC1005X40N")
      (description "Resistor - 1%")
      (fields
        (field (name "MANUFACTURER PART NUMBER") "R0402_10K_1%_0.0625W_100PPM")
        (field (name "MANUFACTURER") "GENERIC")
        (field (name "AUTHOR") "CERN DEM JLC")
      )
      (libsource (lib "Resistors") (part "Resistor - 1%"))
    )
    (comp (ref "R236")
      (value "10k")
      (footprint "RESC1005X40N")
      (description "Resistor - 1%")
      (fields
        (field (name "MANUFACTURER PART NUMBER") "R0402_10K_1%_0.0625W_100PPM")
        (field (name "MANUFACTURER") "GENERIC")
        (field (name "AUTHOR") "CERN DEM JLC")
      )
      (libsource (lib "Resistors") (part "Resistor - 1%"))
    )
    (comp (ref "R237")
      (value "10k")
      (footprint "RESC1005X40N")
      (description "Resistor - 1%")
      (fields
        (field (name "MANUFACTURER PART NUMBER") "R0402_10K_1%_0.0625W_100PPM")
        (field (name "MANUFACTURER") "GENERIC")
        (field (name "AUTHOR") "CERN DEM JLC")
      )
      (libsource (lib "Resistors") (part "Resistor - 1%"))
    )
    (comp (ref "R238")
      (value "10k")
      (footprint "RESC1005X40N")
      (description "Resistor - 1%")
      (fields
        (field (name "MANUFACTURER PART NUMBER") "R0402_10K_1%_0.0625W_100PPM")
        (field (name "MANUFACTURER") "GENERIC")
        (field (name "AUTHOR") "CERN DEM JLC")
      )
      (libsource (lib "Resistors") (part "Resistor - 1%"))
    )
    (comp (ref "R239")
      (value "1k")
      (footprint "RESC1005X40N")
      (description "Resistor - 1%")
      (fields
        (field (name "MANUFACTURER PART NUMBER") "R0402_1K_1%_0.0625W_100PPM")
        (field (name "MANUFACTURER") "GENERIC")
        (field (name "AUTHOR") "CERN DEM JLC")
      )
      (libsource (lib "Resistors") (part "Resistor - 1%"))
    )
    (comp (ref "R240")
      (value "1k")
      (footprint "RESC1005X40N")
      (description "Resistor - 1%")
      (fields
        (field (name "MANUFACTURER PART NUMBER") "R0402_1K_1%_0.0625W_100PPM")
        (field (name "MANUFACTURER") "GENERIC")
        (field (name "AUTHOR") "CERN DEM JLC")
      )
      (libsource (lib "Resistors") (part "Resistor - 1%"))
    )
    (comp (ref "R241")
      (value "2k49")
      (footprint "RESC1608X55N")
      (description "Resistor - 0.1%")
      (fields
        (field (name "PART NUMBER") "R0603_2K49_0.1%_0.063W_10PPM")
        (field (name "POWER") "0.063W")
        (field (name "AUTHOR") "CERN DEM JLC")
      )
      (libsource (lib "Resistors") (part "Resistor - 0.1%"))
    )
    (comp (ref "R242")
      (value "2M49")
      (footprint "RESC1608X55N")
      (description "Resistor - 1%")
      (fields
        (field (name "PART NUMBER") "R0603_2M49_1%_0.1W_100PPM")
        (field (name "POWER") "0.1W")
        (field (name "AUTHOR") "CERN DEM JLC")
      )
      (libsource (lib "Resistors") (part "Resistor - 1%"))
    )
    (comp (ref "R243")
      (value "383k")
      (footprint "RESC1608X55N")
      (description "Resistor - 0.1%")
      (fields
        (field (name "PART NUMBER") "R0603_383K_0.1%_0.063W_25PPM")
        (field (name "POWER") "0.063W")
        (field (name "AUTHOR") "CERN DEM JLC")
      )
      (libsource (lib "Resistors") (part "Resistor - 0.1%"))
    )
    (comp (ref "R244")
      (value "10k")
      (footprint "RESC1005X40N")
      (description "Resistor - 1%")
      (fields
        (field (name "MANUFACTURER PART NUMBER") "R0402_10K_1%_0.0625W_100PPM")
        (field (name "MANUFACTURER") "GENERIC")
        (field (name "AUTHOR") "CERN DEM JLC")
      )
      (libsource (lib "Resistors") (part "Resistor - 1%"))
    )
    (comp (ref "R245")
      (value "10k")
      (footprint "RESC1005X40N")
      (description "Resistor - 1%")
      (fields
        (field (name "MANUFACTURER PART NUMBER") "R0402_10K_1%_0.0625W_100PPM")
        (field (name "MANUFACTURER") "GENERIC")
        (field (name "AUTHOR") "CERN DEM JLC")
      )
      (libsource (lib "Resistors") (part "Resistor - 1%"))
    )
    (comp (ref "T10")
      (value "BC847BV")
      (footprint "SOTFL50P160X60-6N")
      (description "45V, 100mA NPN General Purpose Double Transistor")
      (fields (field (name "MANUFACTURER") "NXP SEMICONDUCTORS") (field (name "AUTHOR") "CERN DEM JLC"))
      (libsource (lib "ICs And Semiconductors") (part "BC847BV"))
    )
    (comp (ref "T11")
      (value "FDMS7608S")
      (footprint "FAIRCHILD_MLP08P")
      (description "30V Dual N-Channel PowerTrench® MOSFET")
      (fields (field (name "MANUFACTURER") "FAIRCHILD SEMICONDUCTOR") (field (name "AUTHOR") "CERN DEM MR"))
      (libsource (lib "ICs And Semiconductors") (part "FDMS7608S"))
    )
    (comp (ref "T12")
      (value "FDMS7608S")
      (footprint "FAIRCHILD_MLP08P")
      (description "30V Dual N-Channel PowerTrench® MOSFET")
      (fields (field (name "MANUFACTURER") "FAIRCHILD SEMICONDUCTOR") (field (name "AUTHOR") "CERN DEM MR"))
      (libsource (lib "ICs And Semiconductors") (part "FDMS7608S"))
    )
    (comp (ref "T13")
      (value "FDMS7608S")
      (footprint "FAIRCHILD_MLP08P")
      (description "30V Dual N-Channel PowerTrench® MOSFET")
      (fields (field (name "MANUFACTURER") "FAIRCHILD SEMICONDUCTOR") (field (name "AUTHOR") "CERN DEM MR"))
      (libsource (lib "ICs And Semiconductors") (part "FDMS7608S"))
    )
    (comp (ref "T14")
      (value "FDMS7608S")
      (footprint "FAIRCHILD_MLP08P")
      (description "30V Dual N-Channel PowerTrench® MOSFET")
      (fields (field (name "MANUFACTURER") "FAIRCHILD SEMICONDUCTOR") (field (name "AUTHOR") "CERN DEM MR"))
      (libsource (lib "ICs And Semiconductors") (part "FDMS7608S"))
    )
    (comp (ref "T15")
      (value "BC847BV")
      (footprint "SOTFL50P160X60-6N")
      (description "45V, 100mA NPN General Purpose Double Transistor")
      (fields (field (name "MANUFACTURER") "NXP SEMICONDUCTORS") (field (name "AUTHOR") "CERN DEM JLC"))
      (libsource (lib "ICs And Semiconductors") (part "BC847BV"))
    )
    (comp (ref "T16")
      (value "BSS138LT1G")
      (footprint "SOT95P240X110-3N")
      (description "N-CHANNEL MOSFET WITH DIODE")
      (fields (field (name "MANUFACTURER") "ON SEMICONDUCTOR") (field (name "AUTHOR") "CERN DEM JLC"))
      (libsource (lib "ICs And Semiconductors") (part "N-MOSFET-D 1G 2S 3D"))
    )
    (comp (ref "TP11")
      (value "Test Point")
      (footprint "TPS127")
      (fields (field (name "PART NUMBER") "SMD_PAD_1.27X1.27MM") (field (name "AUTHOR") "CERN DEM JLC"))
      (libsource (lib "Eletro-mechanical") (part "Test Point"))
    )
    (comp (ref "TP12")
      (value "Test Point")
      (footprint "TPS127")
      (fields (field (name "PART NUMBER") "SMD_PAD_1.27X1.27MM") (field (name "AUTHOR") "CERN DEM JLC"))
      (libsource (lib "Eletro-mechanical") (part "Test Point"))
    )
    (comp (ref "TP13")
      (value "Test Point")
      (footprint "TPS127")
      (fields (field (name "PART NUMBER") "SMD_PAD_1.27X1.27MM") (field (name "AUTHOR") "CERN DEM JLC"))
      (libsource (lib "Eletro-mechanical") (part "Test Point"))
    )
    (comp (ref "TP14")
      (value "Test Point")
      (footprint "TPS127")
      (fields (field (name "PART NUMBER") "SMD_PAD_1.27X1.27MM") (field (name "AUTHOR") "CERN DEM JLC"))
      (libsource (lib "Eletro-mechanical") (part "Test Point"))
    )
    (comp (ref "TP15")
      (value "Test Point")
      (footprint "TPS127")
      (fields (field (name "PART NUMBER") "SMD_PAD_1.27X1.27MM") (field (name "AUTHOR") "CERN DEM JLC"))
      (libsource (lib "Eletro-mechanical") (part "Test Point"))
    )
    (comp (ref "TP16")
      (value "Test Point")
      (footprint "TPS127")
      (fields (field (name "PART NUMBER") "SMD_PAD_1.27X1.27MM") (field (name "AUTHOR") "CERN DEM JLC"))
      (libsource (lib "Eletro-mechanical") (part "Test Point"))
    )
    (comp (ref "TP17")
      (value "Test Point")
      (footprint "TPS127")
      (fields (field (name "PART NUMBER") "SMD_PAD_1.27X1.27MM") (field (name "AUTHOR") "CERN DEM JLC"))
      (libsource (lib "Eletro-mechanical") (part "Test Point"))
    )
    (comp (ref "TP18")
      (value "Test Point")
      (footprint "TPS127")
      (fields (field (name "PART NUMBER") "SMD_PAD_1.27X1.27MM") (field (name "AUTHOR") "CERN DEM JLC"))
      (libsource (lib "Eletro-mechanical") (part "Test Point"))
    )
    (comp (ref "TP19")
      (value "Test Point")
      (footprint "TPS127")
      (fields (field (name "PART NUMBER") "SMD_PAD_1.27X1.27MM") (field (name "AUTHOR") "CERN DEM JLC"))
      (libsource (lib "Eletro-mechanical") (part "Test Point"))
    )
    (comp (ref "TP20")
      (value "Test Point")
      (footprint "TPS127")
      (fields (field (name "PART NUMBER") "SMD_PAD_1.27X1.27MM") (field (name "AUTHOR") "CERN DEM JLC"))
      (libsource (lib "Eletro-mechanical") (part "Test Point"))
    )
    (comp (ref "W1")
      (value "Header 4")
      (footprint "SAMTEC_MTLW-104-07-L-S-250")
      (description "4 Mini Wire-Wrap Contact Strip Header")
      (fields
        (field (name "MANUFACTURER PART NUMBER") "MTLW-104-07-L-S-250")
        (field (name "MANUFACTURER") "SAMTEC")
        (field (name "AUTHOR") "CERN DEM JLC")
      )
      (libsource (lib "Connectors") (part "Wire-Wrap Contact x4"))
    )
  )
  (nets
    (net (code "2") (name "/6V_PGOOD") (class "Default")
      (node (ref "IC43") (pin "7") (pinfunction "PG_7") (pintype "output"))
      (node (ref "R233") (pin "2") (pinfunction "2_2") (pintype "passive"))
    )
    (net (code "3") (name "/AVDD") (class "Default")
      (node (ref "C371") (pin "2") (pinfunction "2_2") (pintype "passive"))
      (node (ref "C372") (pin "2") (pinfunction "2_2") (pintype "passive"))
      (node (ref "IC42") (pin "16") (pinfunction "DVDD_16") (pintype "power_in"))
      (node (ref "IC42") (pin "4") (pinfunction "AVDD_4") (pintype "power_in"))
    )
    (net (code "4") (name "/EN_1V2") (class "Default")
      (node (ref "IC40") (pin "11") (pinfunction "EN_11") (pintype "input"))
      (node (ref "R218") (pin "2") (pinfunction "2_2") (pintype "passive"))
      (node (ref "R223") (pin "1") (pinfunction "1_1") (pintype "passive"))
    )
    (net (code "5") (name "/EN_P0V95") (class "Default")
      (node (ref "IC41") (pin "11") (pinfunction "EN_11") (pintype "input"))
      (node (ref "R221") (pin "2") (pinfunction "2_2") (pintype "passive"))
      (node (ref "R224") (pin "1") (pinfunction "1_1") (pintype "passive"))
    )
    (net (code "6") (name "/LDO5") (class "Default")
      (node (ref "C373") (pin "2") (pinfunction "2_2") (pintype "passive"))
      (node (ref "C374") (pin "2") (pinfunction "2_2") (pintype "passive"))
      (node (ref "C380") (pin "2") (pinfunction "2_2") (pintype "passive"))
      (node (ref "C381") (pin "2") (pinfunction "2_2") (pintype "passive"))
      (node (ref "IC42") (pin "23") (pinfunction "VCCD3-4_23") (pintype "output"))
      (node (ref "IC42") (pin "34") (pinfunction "VCCD1-2_34") (pintype "output"))
      (node (ref "IC42") (pin "44") (pinfunction "LDO5_44") (pintype "output"))
    )
    (net (code "7") (name "/P1V5_LDO_IN") (class "Default")
      (node (ref "C337") (pin "2") (pinfunction "2_2") (pintype "passive"))
      (node (ref "IC40") (pin "5") (pinfunction "IN_5") (pintype "input"))
      (node (ref "IC40") (pin "6") (pinfunction "IN_6") (pintype "input"))
      (node (ref "IC40") (pin "7") (pinfunction "IN_7") (pintype "input"))
      (node (ref "IC40") (pin "8") (pinfunction "IN_8") (pintype "input"))
      (node (ref "L16") (pin "1") (pinfunction "1_1") (pintype "passive"))
    )
    (net (code "8") (name "/P5V0_DCDC") (class "Default")
      (node (ref "C383") (pin "2") (pinfunction "2_2") (pintype "passive"))
      (node (ref "IC43") (pin "10") (pinfunction "VOS_10") (pintype "input"))
      (node (ref "IC43") (pin "8") (pinfunction "SLEEP_8") (pintype "input"))
      (node (ref "L29") (pin "2") (pinfunction "2_2") (pintype "passive"))
      (node (ref "L30") (pin "1") (pinfunction "1_1") (pintype "passive"))
      (node (ref "R242") (pin "2") (pinfunction "2_2") (pintype "passive"))
    )
    (net (code "9") (name "/P6V0_EN") (class "Default")
      (node (ref "R234") (pin "2") (pinfunction "2_2") (pintype "passive"))
    )
    (net (code "10") (name "/P6V0_SW") (class "Default")
      (node (ref "IC43") (pin "9") (pinfunction "SW_9") (pintype "output"))
      (node (ref "L29") (pin "1") (pinfunction "1_1") (pintype "passive"))
    )
    (net (code "11") (name "/PM_SCL") (class "Default")
      (node (ref "IC42") (pin "12") (pinfunction "SCL_12") (pintype "bidirectional"))
      (node (ref "TP12") (pin "1") (pinfunction "1_1") (pintype "bidirectional"))
      (node (ref "W1") (pin "2") (pinfunction "2_2") (pintype "bidirectional"))
    )
    (net (code "12") (name "/PM_SDA") (class "Default")
      (node (ref "IC42") (pin "11") (pinfunction "SDA_11") (pintype "bidirectional"))
      (node (ref "TP11") (pin "1") (pinfunction "1_1") (pintype "bidirectional"))
      (node (ref "W1") (pin "3") (pinfunction "3_3") (pintype "bidirectional"))
    )
    (net (code "13") (name "/PSS_XRP_BST1") (class "Default")
      (node (ref "C336") (pin "2") (pinfunction "2_2") (pintype "passive"))
      (node (ref "IC42") (pin "35") (pinfunction "BST1_35") (pintype "input"))
    )
    (net (code "14") (name "/PSS_XRP_BST2") (class "Default")
      (node (ref "C352") (pin "2") (pinfunction "2_2") (pintype "passive"))
      (node (ref "IC42") (pin "29") (pinfunction "BST2_29") (pintype "input"))
    )
    (net (code "15") (name "/PSS_XRP_BST3") (class "Default")
      (node (ref "C361") (pin "2") (pinfunction "2_2") (pintype "passive"))
      (node (ref "IC42") (pin "24") (pinfunction "BST3_24") (pintype "input"))
    )
    (net (code "16") (name "/PSS_XRP_BST4") (class "Default")
      (node (ref "C368") (pin "2") (pinfunction "2_2") (pintype "passive"))
      (node (ref "IC42") (pin "18") (pinfunction "BST4_18") (pintype "input"))
    )
    (net (code "17") (name "/PSS_XRP_GH1") (class "Default")
      (node (ref "IC42") (pin "36") (pinfunction "GH1_36") (pintype "output"))
      (node (ref "T11") (pin "1") (pinfunction "G1_1") (pintype "passive"))
    )
    (net (code "18") (name "/PSS_XRP_GH2") (class "Default")
      (node (ref "IC42") (pin "30") (pinfunction "GH2_30") (pintype "output"))
      (node (ref "T12") (pin "1") (pinfunction "G1_1") (pintype "passive"))
    )
    (net (code "19") (name "/PSS_XRP_GH3") (class "Default")
      (node (ref "IC42") (pin "25") (pinfunction "GH3_25") (pintype "output"))
      (node (ref "T13") (pin "1") (pinfunction "G1_1") (pintype "passive"))
    )
    (net (code "20") (name "/PSS_XRP_GH4") (class "Default")
      (node (ref "IC42") (pin "19") (pinfunction "GH4_19") (pintype "output"))
      (node (ref "T14") (pin "1") (pinfunction "G1_1") (pintype "passive"))
    )
    (net (code "21") (name "/PSS_XRP_GL1") (class "Default")
      (node (ref "IC42") (pin "38") (pinfunction "GL1_38") (pintype "output"))
      (node (ref "T11") (pin "8") (pinfunction "G2_8") (pintype "passive"))
    )
    (net (code "22") (name "/PSS_XRP_GL2") (class "Default")
      (node (ref "IC42") (pin "32") (pinfunction "GL2_32") (pintype "output"))
      (node (ref "T12") (pin "8") (pinfunction "G2_8") (pintype "passive"))
    )
    (net (code "23") (name "/PSS_XRP_GL3") (class "Default")
      (node (ref "IC42") (pin "27") (pinfunction "GL3_27") (pintype "output"))
      (node (ref "T13") (pin "8") (pinfunction "G2_8") (pintype "passive"))
    )
    (net (code "24") (name "/PSS_XRP_GL4") (class "Default")
      (node (ref "IC42") (pin "21") (pinfunction "GL4_21") (pintype "output"))
      (node (ref "T14") (pin "8") (pinfunction "G2_8") (pintype "passive"))
    )
    (net (code "25") (name "/PSS_XRP_LDO3_3") (class "Default")
      (node (ref "C375") (pin "2") (pinfunction "2_2") (pintype "passive"))
      (node (ref "C376") (pin "2") (pinfunction "2_2") (pintype "passive"))
      (node (ref "IC42") (pin "1") (pinfunction "LDOOUT_1") (pintype "output"))
    )
    (net (code "26") (name "/PSS_XRP_LX1") (class "Default")
      (node (ref "C336") (pin "1") (pinfunction "1_1") (pintype "passive"))
      (node (ref "IC42") (pin "37") (pinfunction "LX1_37") (pintype "input"))
      (node (ref "L19") (pin "1") (pinfunction "1_1") (pintype "passive"))
      (node (ref "T11") (pin "9") (pinfunction "S1D2_9") (pintype "passive"))
    )
    (net (code "27") (name "/PSS_XRP_LX2") (class "Default")
      (node (ref "C352") (pin "1") (pinfunction "1_1") (pintype "passive"))
      (node (ref "IC42") (pin "31") (pinfunction "LX2_31") (pintype "input"))
      (node (ref "L21") (pin "1") (pinfunction "1_1") (pintype "passive"))
      (node (ref "T12") (pin "9") (pinfunction "S1D2_9") (pintype "passive"))
    )
    (net (code "28") (name "/PSS_XRP_LX3") (class "Default")
      (node (ref "C361") (pin "1") (pinfunction "1_1") (pintype "passive"))
      (node (ref "IC42") (pin "26") (pinfunction "LX3_26") (pintype "input"))
      (node (ref "L23") (pin "1") (pinfunction "1_1") (pintype "passive"))
      (node (ref "T13") (pin "9") (pinfunction "S1D2_9") (pintype "passive"))
    )
    (net (code "29") (name "/PSS_XRP_LX4") (class "Default")
      (node (ref "C368") (pin "1") (pinfunction "1_1") (pintype "passive"))
      (node (ref "IC42") (pin "20") (pinfunction "LX4_20") (pintype "input"))
      (node (ref "L27") (pin "1") (pinfunction "1_1") (pintype "passive"))
      (node (ref "T14") (pin "9") (pinfunction "S1D2_9") (pintype "passive"))
    )
    (net (code "30") (name "/PSU_CH_EN") (class "Default")
      (node (ref "IC42") (pin "13") (pinfunction "PSIO0_13") (pintype "output"))
      (node (ref "R228") (pin "2") (pinfunction "2_2") (pintype "passive"))
    )
    (net (code "31") (name "/PSU_EN") (class "Default")
      (node (ref "R222") (pin "2") (pinfunction "2_2") (pintype "passive"))
    )
    (net (code "32") (name "/TPS74401RGW_PG1") (class "Default")
      (node (ref "IC41") (pin "9") (pinfunction "PG_9") (pintype "output"))
      (node (ref "R215") (pin "1") (pinfunction "1_1") (pintype "passive"))
      (node (ref "R227") (pin "1") (pinfunction "1_1") (pintype "passive"))
    )
    (net (code "33") (name "/TPS74401RGW_PG2") (class "Default")
      (node (ref "IC40") (pin "9") (pinfunction "PG_9") (pintype "output"))
      (node (ref "R214") (pin "1") (pinfunction "1_1") (pintype "passive"))
      (node (ref "R226") (pin "1") (pinfunction "1_1") (pintype "passive"))
    )
    (net (code "34") (name "/XR77129ILB_F_VOUT1") (class "Default")
      (node (ref "C344") (pin "2") (pinfunction "2_2") (pintype "passive"))
      (node (ref "C345") (pin "2") (pinfunction "2_2") (pintype "passive"))
      (node (ref "C346") (pin "2") (pinfunction "2_2") (pintype "passive"))
      (node (ref "C347") (pin "2") (pinfunction "2_2") (pintype "passive"))
      (node (ref "C348") (pin "2") (pinfunction "2_2") (pintype "passive"))
      (node (ref "IC42") (pin "5") (pinfunction "VOUT1_5") (pintype "input"))
      (node (ref "L18") (pin "2") (pinfunction "2_2") (pintype "passive"))
      (node (ref "L19") (pin "2") (pinfunction "2_2") (pintype "passive"))
      (node (ref "L20") (pin "1") (pinfunction "1_1") (pintype "passive"))
    )
    (net (code "35") (name "/XR77129ILB_F_VOUT2") (class "Default")
      (node (ref "C358") (pin "2") (pinfunction "2_2") (pintype "passive"))
      (node (ref "C359") (pin "2") (pinfunction "2_2") (pintype "passive"))
      (node (ref "C360") (pin "2") (pinfunction "2_2") (pintype "passive"))
      (node (ref "IC42") (pin "6") (pinfunction "VOUT2_6") (pintype "input"))
      (node (ref "L21") (pin "2") (pinfunction "2_2") (pintype "passive"))
      (node (ref "L22") (pin "1") (pinfunction "1_1") (pintype "passive"))
    )
    (net (code "36") (name "/XR77129ILB_F_VOUT3") (class "Default")
      (node (ref "C364") (pin "2") (pinfunction "2_2") (pintype "passive"))
      (node (ref "C365") (pin "2") (pinfunction "2_2") (pintype "passive"))
      (node (ref "C366") (pin "2") (pinfunction "2_2") (pintype "passive"))
      (node (ref "IC42") (pin "7") (pinfunction "VOUT3_7") (pintype "input"))
      (node (ref "L23") (pin "2") (pinfunction "2_2") (pintype "passive"))
      (node (ref "L24") (pin "1") (pinfunction "1_1") (pintype "passive"))
    )
    (net (code "37") (name "/XR77129ILB_F_VOUT4") (class "Default")
      (node (ref "C377") (pin "2") (pinfunction "2_2") (pintype "passive"))
      (node (ref "C378") (pin "2") (pinfunction "2_2") (pintype "passive"))
      (node (ref "C379") (pin "2") (pinfunction "2_2") (pintype "passive"))
      (node (ref "IC42") (pin "8") (pinfunction "VOUT4_8") (pintype "input"))
      (node (ref "L27") (pin "2") (pinfunction "2_2") (pintype "passive"))
      (node (ref "L28") (pin "1") (pinfunction "1_1") (pintype "passive"))
    )
    (net (code "39") (name "GND") (class "Default")
      (node (ref "C337") (pin "1") (pinfunction "1_1") (pintype "passive"))
      (node (ref "C338") (pin "1") (pinfunction "1_1") (pintype "passive"))
      (node (ref "C339") (pin "1") (pinfunction "1_1") (pintype "passive"))
      (node (ref "C340") (pin "1") (pinfunction "1_1") (pintype "passive"))
      (node (ref "C341") (pin "1") (pinfunction "1_1") (pintype "passive"))
      (node (ref "C342") (pin "1") (pinfunction "1_1") (pintype "passive"))
      (node (ref "C343") (pin "1") (pinfunction "1_1") (pintype "passive"))
      (node (ref "C344") (pin "1") (pinfunction "1_1") (pintype "passive"))
      (node (ref "C345") (pin "1") (pinfunction "1_1") (pintype "passive"))
      (node (ref "C346") (pin "1") (pinfunction "1_1") (pintype "passive"))
      (node (ref "C347") (pin "1") (pinfunction "1_1") (pintype "passive"))
      (node (ref "C348") (pin "1") (pinfunction "1_1") (pintype "passive"))
      (node (ref "C349") (pin "1") (pinfunction "1_1") (pintype "passive"))
      (node (ref "C350") (pin "1") (pinfunction "1_1") (pintype "passive"))
      (node (ref "C351") (pin "2") (pinfunction "2_2") (pintype "passive"))
      (node (ref "C353") (pin "1") (pinfunction "1_1") (pintype "passive"))
      (node (ref "C354") (pin "1") (pinfunction "1_1") (pintype "passive"))
      (node (ref "C355") (pin "1") (pinfunction "1_1") (pintype "passive"))
      (node (ref "C356") (pin "1") (pinfunction "1_1") (pintype "passive"))
      (node (ref "C357") (pin "1") (pinfunction "1_1") (pintype "passive"))
      (node (ref "C358") (pin "1") (pinfunction "1_1") (pintype "passive"))
      (node (ref "C359") (pin "1") (pinfunction "1_1") (pintype "passive"))
      (node (ref "C360") (pin "1") (pinfunction "1_1") (pintype "passive"))
      (node (ref "C362") (pin "1") (pinfunction "1_1") (pintype "passive"))
      (node (ref "C363") (pin "1") (pinfunction "1_1") (pintype "passive"))
      (node (ref "C364") (pin "1") (pinfunction "1_1") (pintype "passive"))
      (node (ref "C365") (pin "1") (pinfunction "1_1") (pintype "passive"))
      (node (ref "C366") (pin "1") (pinfunction "1_1") (pintype "passive"))
      (node (ref "C367") (pin "1") (pinfunction "1_1") (pintype "passive"))
      (node (ref "C369") (pin "1") (pinfunction "1_1") (pintype "passive"))
      (node (ref "C370") (pin "1") (pinfunction "1_1") (pintype "passive"))
      (node (ref "C371") (pin "1") (pinfunction "1_1") (pintype "passive"))
      (node (ref "C372") (pin "1") (pinfunction "1_1") (pintype "passive"))
      (node (ref "C373") (pin "1") (pinfunction "1_1") (pintype "passive"))
      (node (ref "C374") (pin "1") (pinfunction "1_1") (pintype "passive"))
      (node (ref "C375") (pin "1") (pinfunction "1_1") (pintype "passive"))
      (node (ref "C376") (pin "1") (pinfunction "1_1") (pintype "passive"))
      (node (ref "C377") (pin "1") (pinfunction "1_1") (pintype "passive"))
      (node (ref "C378") (pin "1") (pinfunction "1_1") (pintype "passive"))
      (node (ref "C379") (pin "1") (pinfunction "1_1") (pintype "passive"))
      (node (ref "C380") (pin "1") (pinfunction "1_1") (pintype "passive"))
      (node (ref "C381") (pin "1") (pinfunction "1_1") (pintype "passive"))
      (node (ref "C382") (pin "1") (pinfunction "1_1") (pintype "passive"))
      (node (ref "C383") (pin "1") (pinfunction "1_1") (pintype "passive"))
      (node (ref "C384") (pin "1") (pinfunction "1_1") (pintype "passive"))
      (node (ref "C385") (pin "1") (pinfunction "1_1") (pintype "passive"))
      (node (ref "IC40") (pin "12") (pinfunction "GND_12") (pintype "power_in"))
      (node (ref "IC40") (pin "21") (pinfunction "EP_21") (pintype "power_in"))
      (node (ref "IC41") (pin "12") (pinfunction "GND_12") (pintype "power_in"))
      (node (ref "IC41") (pin "21") (pinfunction "EP_21") (pintype "power_in"))
      (node (ref "IC42") (pin "17") (pinfunction "DGND_17") (pintype "power_in"))
      (node (ref "IC42") (pin "2") (pinfunction "AGND_2") (pintype "power_in"))
      (node (ref "IC42") (pin "42") (pinfunction "BFB_42") (pintype "input"))
      (node (ref "IC42") (pin "45") (pinfunction "AGND_45") (pintype "power_in"))
      (node (ref "IC43") (pin "1") (pinfunction "PGND_1") (pintype "power_in"))
      (node (ref "IC43") (pin "11") (pinfunction "EP_11") (pintype "power_in"))
      (node (ref "IC43") (pin "6") (pinfunction "AGND_6") (pintype "power_in"))
      (node (ref "LD10") (pin "1") (pinfunction "C_1") (pintype "passive"))
      (node (ref "LD11") (pin "1") (pinfunction "C_1") (pintype "passive"))
      (node (ref "LD8") (pin "1") (pinfunction "C_1") (pintype "passive"))
      (node (ref "LD9") (pin "1") (pinfunction "C_1") (pintype "passive"))
      (node (ref "R217") (pin "1") (pinfunction "1_1") (pintype "passive"))
      (node (ref "R218") (pin "1") (pinfunction "1_1") (pintype "passive"))
      (node (ref "R220") (pin "1") (pinfunction "1_1") (pintype "passive"))
      (node (ref "R221") (pin "1") (pinfunction "1_1") (pintype "passive"))
      (node (ref "R225") (pin "2") (pinfunction "2_2") (pintype "passive"))
      (node (ref "R228") (pin "1") (pinfunction "1_1") (pintype "passive"))
      (node (ref "R229") (pin "2") (pinfunction "2_2") (pintype "passive"))
      (node (ref "R230") (pin "2") (pinfunction "2_2") (pintype "passive"))
      (node (ref "R232") (pin "2") (pinfunction "2_2") (pintype "passive"))
      (node (ref "R243") (pin "1") (pinfunction "1_1") (pintype "passive"))
      (node (ref "T10") (pin "4") (pinfunction "E_4") (pintype "passive"))
      (node (ref "T11") (pin "5") (pinfunction "S2_5") (pintype "passive"))
      (node (ref "T11") (pin "6") (pinfunction "S2_6") (pintype "passive"))
      (node (ref "T11") (pin "7") (pinfunction "S2_7") (pintype "passive"))
      (node (ref "T12") (pin "5") (pinfunction "S2_5") (pintype "passive"))
      (node (ref "T12") (pin "6") (pinfunction "S2_6") (pintype "passive"))
      (node (ref "T12") (pin "7") (pinfunction "S2_7") (pintype "passive"))
      (node (ref "T13") (pin "5") (pinfunction "S2_5") (pintype "passive"))
      (node (ref "T13") (pin "6") (pinfunction "S2_6") (pintype "passive"))
      (node (ref "T13") (pin "7") (pinfunction "S2_7") (pintype "passive"))
      (node (ref "T14") (pin "5") (pinfunction "S2_5") (pintype "passive"))
      (node (ref "T14") (pin "6") (pinfunction "S2_6") (pintype "passive"))
      (node (ref "T14") (pin "7") (pinfunction "S2_7") (pintype "passive"))
      (node (ref "T15") (pin "1") (pinfunction "E_1") (pintype "passive"))
      (node (ref "T16") (pin "2") (pinfunction "S_2") (pintype "passive"))
      (node (ref "W1") (pin "4") (pinfunction "4_4") (pintype "bidirectional"))
    )
    (net (code "40") (name "MGTAVCC") (class "Default")
      (node (ref "L20") (pin "2") (pinfunction "2_2") (pintype "passive"))
    )
    (net (code "41") (name "MGTAVTT") (class "Default")
      (node (ref "L15") (pin "2") (pinfunction "2_2") (pintype "passive"))
    )
    (net (code "42") (name "MGTVCCAUX") (class "Default")
      (node (ref "L26") (pin "1") (pinfunction "1_1") (pintype "passive"))
    )
    (net (code "43") (name "Net-(D27-A)") (class "Default")
      (node (ref "D27") (pin "2") (pinfunction "A_2") (pintype "passive"))
      (node (ref "IC42") (pin "40") (pinfunction "ENABLE_40") (pintype "input"))
      (node (ref "R222") (pin "1") (pinfunction "1_1") (pintype "passive"))
      (node (ref "W1") (pin "1") (pinfunction "1_1") (pintype "bidirectional"))
    )
    (net (code "44") (name "Net-(IC40-FB)") (class "Default")
      (node (ref "IC40") (pin "16") (pinfunction "FB_16") (pintype "output"))
      (node (ref "R216") (pin "1") (pinfunction "1_1") (pintype "passive"))
      (node (ref "R217") (pin "2") (pinfunction "2_2") (pintype "passive"))
    )
    (net (code "45") (name "Net-(IC40-SS)") (class "Default")
      (node (ref "C343") (pin "2") (pinfunction "2_2") (pintype "passive"))
      (node (ref "IC40") (pin "15") (pinfunction "SS_15") (pintype "passive"))
    )
    (net (code "46") (name "Net-(IC41-FB)") (class "Default")
      (node (ref "IC41") (pin "16") (pinfunction "FB_16") (pintype "output"))
      (node (ref "R219") (pin "1") (pinfunction "1_1") (pintype "passive"))
      (node (ref "R220") (pin "2") (pinfunction "2_2") (pintype "passive"))
    )
    (net (code "47") (name "Net-(IC41-SS)") (class "Default")
      (node (ref "C351") (pin "1") (pinfunction "1_1") (pintype "passive"))
      (node (ref "IC41") (pin "15") (pinfunction "SS_15") (pintype "passive"))
    )
    (net (code "48") (name "Net-(IC42-CPLL)") (class "Default")
      (node (ref "C367") (pin "2") (pinfunction "2_2") (pintype "passive"))
      (node (ref "IC42") (pin "3") (pinfunction "CPLL_3") (pintype "passive"))
    )
    (net (code "49") (name "Net-(IC42-GL_RTN1)") (class "Default")
      (node (ref "IC42") (pin "39") (pinfunction "GL_RTN1_39") (pintype "power_in"))
      (node (ref "R225") (pin "1") (pinfunction "1_1") (pintype "passive"))
    )
    (net (code "50") (name "Net-(IC42-GL_RTN2)") (class "Default")
      (node (ref "IC42") (pin "33") (pinfunction "GL_RTN2_33") (pintype "power_in"))
      (node (ref "R229") (pin "1") (pinfunction "1_1") (pintype "passive"))
    )
    (net (code "51") (name "Net-(IC42-GL_RTN3)") (class "Default")
      (node (ref "IC42") (pin "28") (pinfunction "GL_RTN3_28") (pintype "power_in"))
      (node (ref "R230") (pin "1") (pinfunction "1_1") (pintype "passive"))
    )
    (net (code "52") (name "Net-(IC42-GL_RTN4)") (class "Default")
      (node (ref "IC42") (pin "22") (pinfunction "GL_RTN4_22") (pintype "power_in"))
      (node (ref "R232") (pin "1") (pinfunction "1_1") (pintype "passive"))
    )
    (net (code "53") (name "Net-(IC42-GPIO0)") (class "Default")
      (node (ref "IC42") (pin "9") (pinfunction "GPIO0_9") (pintype "bidirectional"))
      (node (ref "R223") (pin "2") (pinfunction "2_2") (pintype "passive"))
    )
    (net (code "54") (name "Net-(IC42-GPIO1)") (class "Default")
      (node (ref "IC42") (pin "10") (pinfunction "GPIO1_10") (pintype "bidirectional"))
      (node (ref "R224") (pin "2") (pinfunction "2_2") (pintype "passive"))
    )
    (net (code "55") (name "Net-(IC42-PSIO1)") (class "Default")
      (node (ref "IC42") (pin "14") (pinfunction "PSIO1_14") (pintype "output"))
      (node (ref "R226") (pin "2") (pinfunction "2_2") (pintype "passive"))
    )
    (net (code "56") (name "Net-(IC42-PSIO2)") (class "Default")
      (node (ref "IC42") (pin "15") (pinfunction "PSIO2_15") (pintype "output"))
      (node (ref "R227") (pin "2") (pinfunction "2_2") (pintype "passive"))
    )
    (net (code "57") (name "Net-(IC42-V5EXT)") (class "Default")
      (node (ref "IC42") (pin "43") (pinfunction "V5EXT_43") (pintype "input"))
      (node (ref "R231") (pin "1") (pinfunction "1_1") (pintype "passive"))
    )
    (net (code "58") (name "Net-(IC43-EN)") (class "Default")
      (node (ref "IC43") (pin "3") (pinfunction "EN_3") (pintype "input"))
      (node (ref "R234") (pin "1") (pinfunction "1_1") (pintype "passive"))
    )
    (net (code "59") (name "Net-(IC43-FB)") (class "Default")
      (node (ref "IC43") (pin "5") (pinfunction "FB_5") (pintype "input"))
      (node (ref "R242") (pin "1") (pinfunction "1_1") (pintype "passive"))
      (node (ref "R243") (pin "2") (pinfunction "2_2") (pintype "passive"))
    )
    (net (code "60") (name "Net-(LD5-A)") (class "Default")
      (node (ref "LD5") (pin "2") (pinfunction "A_2") (pintype "passive"))
      (node (ref "R235") (pin "1") (pinfunction "1_1") (pintype "passive"))
    )
    (net (code "61") (name "Net-(LD5-C)") (class "Default")
      (node (ref "LD5") (pin "1") (pinfunction "C_1") (pintype "passive"))
      (node (ref "T15") (pin "6") (pinfunction "C_6") (pintype "passive"))
    )
    (net (code "62") (name "Net-(LD6-A)") (class "Default")
      (node (ref "LD6") (pin "2") (pinfunction "A_2") (pintype "passive"))
      (node (ref "R236") (pin "1") (pinfunction "1_1") (pintype "passive"))
    )
    (net (code "63") (name "Net-(LD6-C)") (class "Default")
      (node (ref "LD6") (pin "1") (pinfunction "C_1") (pintype "passive"))
      (node (ref "T10") (pin "3") (pinfunction "C_3") (pintype "passive"))
    )
    (net (code "64") (name "Net-(LD7-A)") (class "Default")
      (node (ref "LD7") (pin "2") (pinfunction "A_2") (pintype "passive"))
      (node (ref "R237") (pin "1") (pinfunction "1_1") (pintype "passive"))
    )
    (net (code "65") (name "Net-(LD7-C)") (class "Default")
      (node (ref "LD7") (pin "1") (pinfunction "C_1") (pintype "passive"))
      (node (ref "T16") (pin "3") (pinfunction "D_3") (pintype "passive"))
    )
    (net (code "66") (name "Net-(LD8-A)") (class "Default")
      (node (ref "LD8") (pin "2") (pinfunction "A_2") (pintype "passive"))
      (node (ref "R238") (pin "1") (pinfunction "1_1") (pintype "passive"))
    )
    (net (code "67") (name "Net-(LD9-A)") (class "Default")
      (node (ref "LD9") (pin "2") (pinfunction "A_2") (pintype "passive"))
      (node (ref "R239") (pin "1") (pinfunction "1_1") (pintype "passive"))
    )
    (net (code "68") (name "Net-(LD10-A)") (class "Default")
      (node (ref "LD10") (pin "2") (pinfunction "A_2") (pintype "passive"))
      (node (ref "R240") (pin "1") (pinfunction "1_1") (pintype "passive"))
    )
    (net (code "69") (name "Net-(LD11-A)") (class "Default")
      (node (ref "LD11") (pin "2") (pinfunction "A_2") (pintype "passive"))
      (node (ref "R241") (pin "1") (pinfunction "1_1") (pintype "passive"))
    )
    (net (code "70") (name "Net-(T10B-B)") (class "Default")
      (node (ref "R245") (pin "2") (pinfunction "2_2") (pintype "passive"))
      (node (ref "T10") (pin "5") (pinfunction "B_5") (pintype "passive"))
    )
    (net (code "71") (name "Net-(T15A-B)") (class "Default")
      (node (ref "R244") (pin "2") (pinfunction "2_2") (pintype "passive"))
      (node (ref "T15") (pin "2") (pinfunction "B_2") (pintype "passive"))
    )
    (net (code "72") (name "P0V95") (class "Default")
      (node (ref "C349") (pin "2") (pinfunction "2_2") (pintype "passive"))
      (node (ref "IC41") (pin "1") (pinfunction "OUT_1") (pintype "power_in"))
      (node (ref "IC41") (pin "18") (pinfunction "OUT_18") (pintype "power_in"))
      (node (ref "IC41") (pin "19") (pinfunction "OUT_19") (pintype "power_in"))
      (node (ref "IC41") (pin "20") (pinfunction "OUT_20") (pintype "power_in"))
      (node (ref "L17") (pin "1") (pinfunction "1_1") (pintype "passive"))
      (node (ref "R219") (pin "2") (pinfunction "2_2") (pintype "passive"))
      (node (ref "R244") (pin "1") (pinfunction "1_1") (pintype "passive"))
      (node (ref "TP13") (pin "1") (pinfunction "1_1") (pintype "bidirectional"))
    )
    (net (code "73") (name "P1V0") (class "Default")
      (node (ref "L18") (pin "1") (pinfunction "1_1") (pintype "passive"))
      (node (ref "TP14") (pin "1") (pinfunction "1_1") (pintype "bidirectional"))
    )
    (net (code "74") (name "P1V2") (class "Default")
      (node (ref "C340") (pin "2") (pinfunction "2_2") (pintype "passive"))
      (node (ref "C341") (pin "2") (pinfunction "2_2") (pintype "passive"))
      (node (ref "IC40") (pin "1") (pinfunction "OUT_1") (pintype "power_in"))
      (node (ref "IC40") (pin "18") (pinfunction "OUT_18") (pintype "power_in"))
      (node (ref "IC40") (pin "19") (pinfunction "OUT_19") (pintype "power_in"))
      (node (ref "IC40") (pin "20") (pinfunction "OUT_20") (pintype "power_in"))
      (node (ref "IC41") (pin "5") (pinfunction "IN_5") (pintype "input"))
      (node (ref "IC41") (pin "6") (pinfunction "IN_6") (pintype "input"))
      (node (ref "IC41") (pin "7") (pinfunction "IN_7") (pintype "input"))
      (node (ref "IC41") (pin "8") (pinfunction "IN_8") (pintype "input"))
      (node (ref "L15") (pin "1") (pinfunction "1_1") (pintype "passive"))
      (node (ref "R216") (pin "2") (pinfunction "2_2") (pintype "passive"))
      (node (ref "TP15") (pin "1") (pinfunction "1_1") (pintype "bidirectional"))
    )
    (net (code "75") (name "P1V5") (class "Default")
      (node (ref "L16") (pin "2") (pinfunction "2_2") (pintype "passive"))
      (node (ref "L28") (pin "2") (pinfunction "2_2") (pintype "passive"))
      (node (ref "R245") (pin "1") (pinfunction "1_1") (pintype "passive"))
      (node (ref "TP16") (pin "1") (pinfunction "1_1") (pintype "bidirectional"))
    )
    (net (code "76") (name "P1V8") (class "Default")
      (node (ref "L24") (pin "2") (pinfunction "2_2") (pintype "passive"))
      (node (ref "L25") (pin "1") (pinfunction "1_1") (pintype "passive"))
      (node (ref "L26") (pin "2") (pinfunction "2_2") (pintype "passive"))
      (node (ref "T16") (pin "1") (pinfunction "G_1") (pintype "passive"))
      (node (ref "TP17") (pin "1") (pinfunction "1_1") (pintype "bidirectional"))
    )
    (net (code "77") (name "P3V3") (class "Default")
      (node (ref "L22") (pin "2") (pinfunction "2_2") (pintype "passive"))
      (node (ref "R239") (pin "2") (pinfunction "2_2") (pintype "passive"))
      (node (ref "TP18") (pin "1") (pinfunction "1_1") (pintype "bidirectional"))
    )
    (net (code "78") (name "P3V3MP") (class "Default")
      (node (ref "D27") (pin "1") (pinfunction "C_1") (pintype "passive"))
      (node (ref "R214") (pin "2") (pinfunction "2_2") (pintype "passive"))
      (node (ref "R215") (pin "2") (pinfunction "2_2") (pintype "passive"))
      (node (ref "R233") (pin "1") (pinfunction "1_1") (pintype "passive"))
      (node (ref "R240") (pin "2") (pinfunction "2_2") (pintype "passive"))
    )
    (net (code "79") (name "P5V0") (class "Default")
      (node (ref "C342") (pin "2") (pinfunction "2_2") (pintype "passive"))
      (node (ref "C350") (pin "2") (pinfunction "2_2") (pintype "passive"))
      (node (ref "IC40") (pin "10") (pinfunction "BIAS_10") (pintype "input"))
      (node (ref "IC41") (pin "10") (pinfunction "BIAS_10") (pintype "input"))
      (node (ref "R231") (pin "2") (pinfunction "2_2") (pintype "passive"))
    )
    (net (code "80") (name "P6V0") (class "Default")
      (node (ref "C384") (pin "2") (pinfunction "2_2") (pintype "passive"))
      (node (ref "L30") (pin "2") (pinfunction "2_2") (pintype "passive"))
      (node (ref "R241") (pin "2") (pinfunction "2_2") (pintype "passive"))
      (node (ref "TP19") (pin "1") (pinfunction "1_1") (pintype "bidirectional"))
    )
    (net (code "81") (name "P12V0") (class "Default")
      (node (ref "C338") (pin "2") (pinfunction "2_2") (pintype "passive"))
      (node (ref "C339") (pin "2") (pinfunction "2_2") (pintype "passive"))
      (node (ref "C353") (pin "2") (pinfunction "2_2") (pintype "passive"))
      (node (ref "C354") (pin "2") (pinfunction "2_2") (pintype "passive"))
      (node (ref "C355") (pin "2") (pinfunction "2_2") (pintype "passive"))
      (node (ref "C356") (pin "2") (pinfunction "2_2") (pintype "passive"))
      (node (ref "C357") (pin "2") (pinfunction "2_2") (pintype "passive"))
      (node (ref "C362") (pin "2") (pinfunction "2_2") (pintype "passive"))
      (node (ref "C363") (pin "2") (pinfunction "2_2") (pintype "passive"))
      (node (ref "C369") (pin "2") (pinfunction "2_2") (pintype "passive"))
      (node (ref "C370") (pin "2") (pinfunction "2_2") (pintype "passive"))
      (node (ref "C382") (pin "2") (pinfunction "2_2") (pintype "passive"))
      (node (ref "C385") (pin "2") (pinfunction "2_2") (pintype "passive"))
      (node (ref "IC42") (pin "41") (pinfunction "VCC_41") (pintype "power_in"))
      (node (ref "IC43") (pin "2") (pinfunction "VIN_2") (pintype "input"))
      (node (ref "R235") (pin "2") (pinfunction "2_2") (pintype "passive"))
      (node (ref "R236") (pin "2") (pinfunction "2_2") (pintype "passive"))
      (node (ref "R237") (pin "2") (pinfunction "2_2") (pintype "passive"))
      (node (ref "R238") (pin "2") (pinfunction "2_2") (pintype "passive"))
      (node (ref "T11") (pin "2") (pinfunction "D1_2") (pintype "passive"))
      (node (ref "T11") (pin "3") (pinfunction "D1_3") (pintype "passive"))
      (node (ref "T11") (pin "4") (pinfunction "D1_4") (pintype "passive"))
      (node (ref "T12") (pin "2") (pinfunction "D1_2") (pintype "passive"))
      (node (ref "T12") (pin "3") (pinfunction "D1_3") (pintype "passive"))
      (node (ref "T12") (pin "4") (pinfunction "D1_4") (pintype "passive"))
      (node (ref "T13") (pin "2") (pinfunction "D1_2") (pintype "passive"))
      (node (ref "T13") (pin "3") (pinfunction "D1_3") (pintype "passive"))
      (node (ref "T13") (pin "4") (pinfunction "D1_4") (pintype "passive"))
      (node (ref "T14") (pin "2") (pinfunction "D1_2") (pintype "passive"))
      (node (ref "T14") (pin "3") (pinfunction "D1_3") (pintype "passive"))
      (node (ref "T14") (pin "4") (pinfunction "D1_4") (pintype "passive"))
    )
    (net (code "82") (name "VCCAUX") (class "Default")
      (node (ref "L25") (pin "2") (pinfunction "2_2") (pintype "passive"))
    )
    (net (code "83") (name "VCCBRAM") (class "Default")
      (node (ref "L17") (pin "2") (pinfunction "2_2") (pintype "passive"))
    )
    (net (code "84") (name "VCCINT") (class "Default")
      (node (ref "TP20") (pin "1") (pinfunction "1_1") (pintype "bidirectional"))
    )
    (net (code "85") (name "unconnected-(IC40-NC-Pad2)") (class "Default")
      (node (ref "IC40") (pin "2") (pinfunction "NC_2") (pintype "passive"))
    )
    (net (code "86") (name "unconnected-(IC40-NC-Pad3)") (class "Default")
      (node (ref "IC40") (pin "3") (pinfunction "NC_3") (pintype "passive"))
    )
    (net (code "87") (name "unconnected-(IC40-NC-Pad4)") (class "Default")
      (node (ref "IC40") (pin "4") (pinfunction "NC_4") (pintype "passive"))
    )
    (net (code "88") (name "unconnected-(IC40-NC-Pad13)") (class "Default")
      (node (ref "IC40") (pin "13") (pinfunction "NC_13") (pintype "passive"))
    )
    (net (code "89") (name "unconnected-(IC40-NC-Pad14)") (class "Default")
      (node (ref "IC40") (pin "14") (pinfunction "NC_14") (pintype "passive"))
    )
    (net (code "90") (name "unconnected-(IC40-NC-Pad17)") (class "Default")
      (node (ref "IC40") (pin "17") (pinfunction "NC_17") (pintype "passive"))
    )
    (net (code "91") (name "unconnected-(IC41-NC-Pad2)") (class "Default")
      (node (ref "IC41") (pin "2") (pinfunction "NC_2") (pintype "passive+no_connect"))
    )
    (net (code "92") (name "unconnected-(IC41-NC-Pad3)") (class "Default")
      (node (ref "IC41") (pin "3") (pinfunction "NC_3") (pintype "passive+no_connect"))
    )
    (net (code "93") (name "unconnected-(IC41-NC-Pad4)") (class "Default")
      (node (ref "IC41") (pin "4") (pinfunction "NC_4") (pintype "passive+no_connect"))
    )
    (net (code "94") (name "unconnected-(IC41-NC-Pad13)") (class "Default")
      (node (ref "IC41") (pin "13") (pinfunction "NC_13") (pintype "passive+no_connect"))
    )
    (net (code "95") (name "unconnected-(IC41-NC-Pad14)") (class "Default")
      (node (ref "IC41") (pin "14") (pinfunction "NC_14") (pintype "passive+no_connect"))
    )
    (net (code "96") (name "unconnected-(IC41-NC-Pad17)") (class "Default")
      (node (ref "IC41") (pin "17") (pinfunction "NC_17") (pintype "passive+no_connect"))
    )
    (net (code "97") (name "unconnected-(IC43-NC-Pad4)") (class "Default")
      (node (ref "IC43") (pin "4") (pinfunction "NC_4") (pintype "passive+no_connect"))
    )
    (net (code "98") (name "unconnected-(T11-D1-Pad10)") (class "Default")
      (node (ref "T11") (pin "10") (pinfunction "D1_10") (pintype "passive"))
    )
    (net (code "99") (name "unconnected-(T12-D1-Pad10)") (class "Default")
      (node (ref "T12") (pin "10") (pinfunction "D1_10") (pintype "passive"))
    )
    (net (code "100") (name "unconnected-(T13-D1-Pad10)") (class "Default")
      (node (ref "T13") (pin "10") (pinfunction "D1_10") (pintype "passive"))
    )
    (net (code "101") (name "unconnected-(T14-D1-Pad10)") (class "Default")
      (node (ref "T14") (pin "10") (pinfunction "D1_10") (pintype "passive"))
    )
  )
)
